# EEZ_DIB_MCU_r1B2.net
KiCad netlist of a schematic drawn in EAGLE
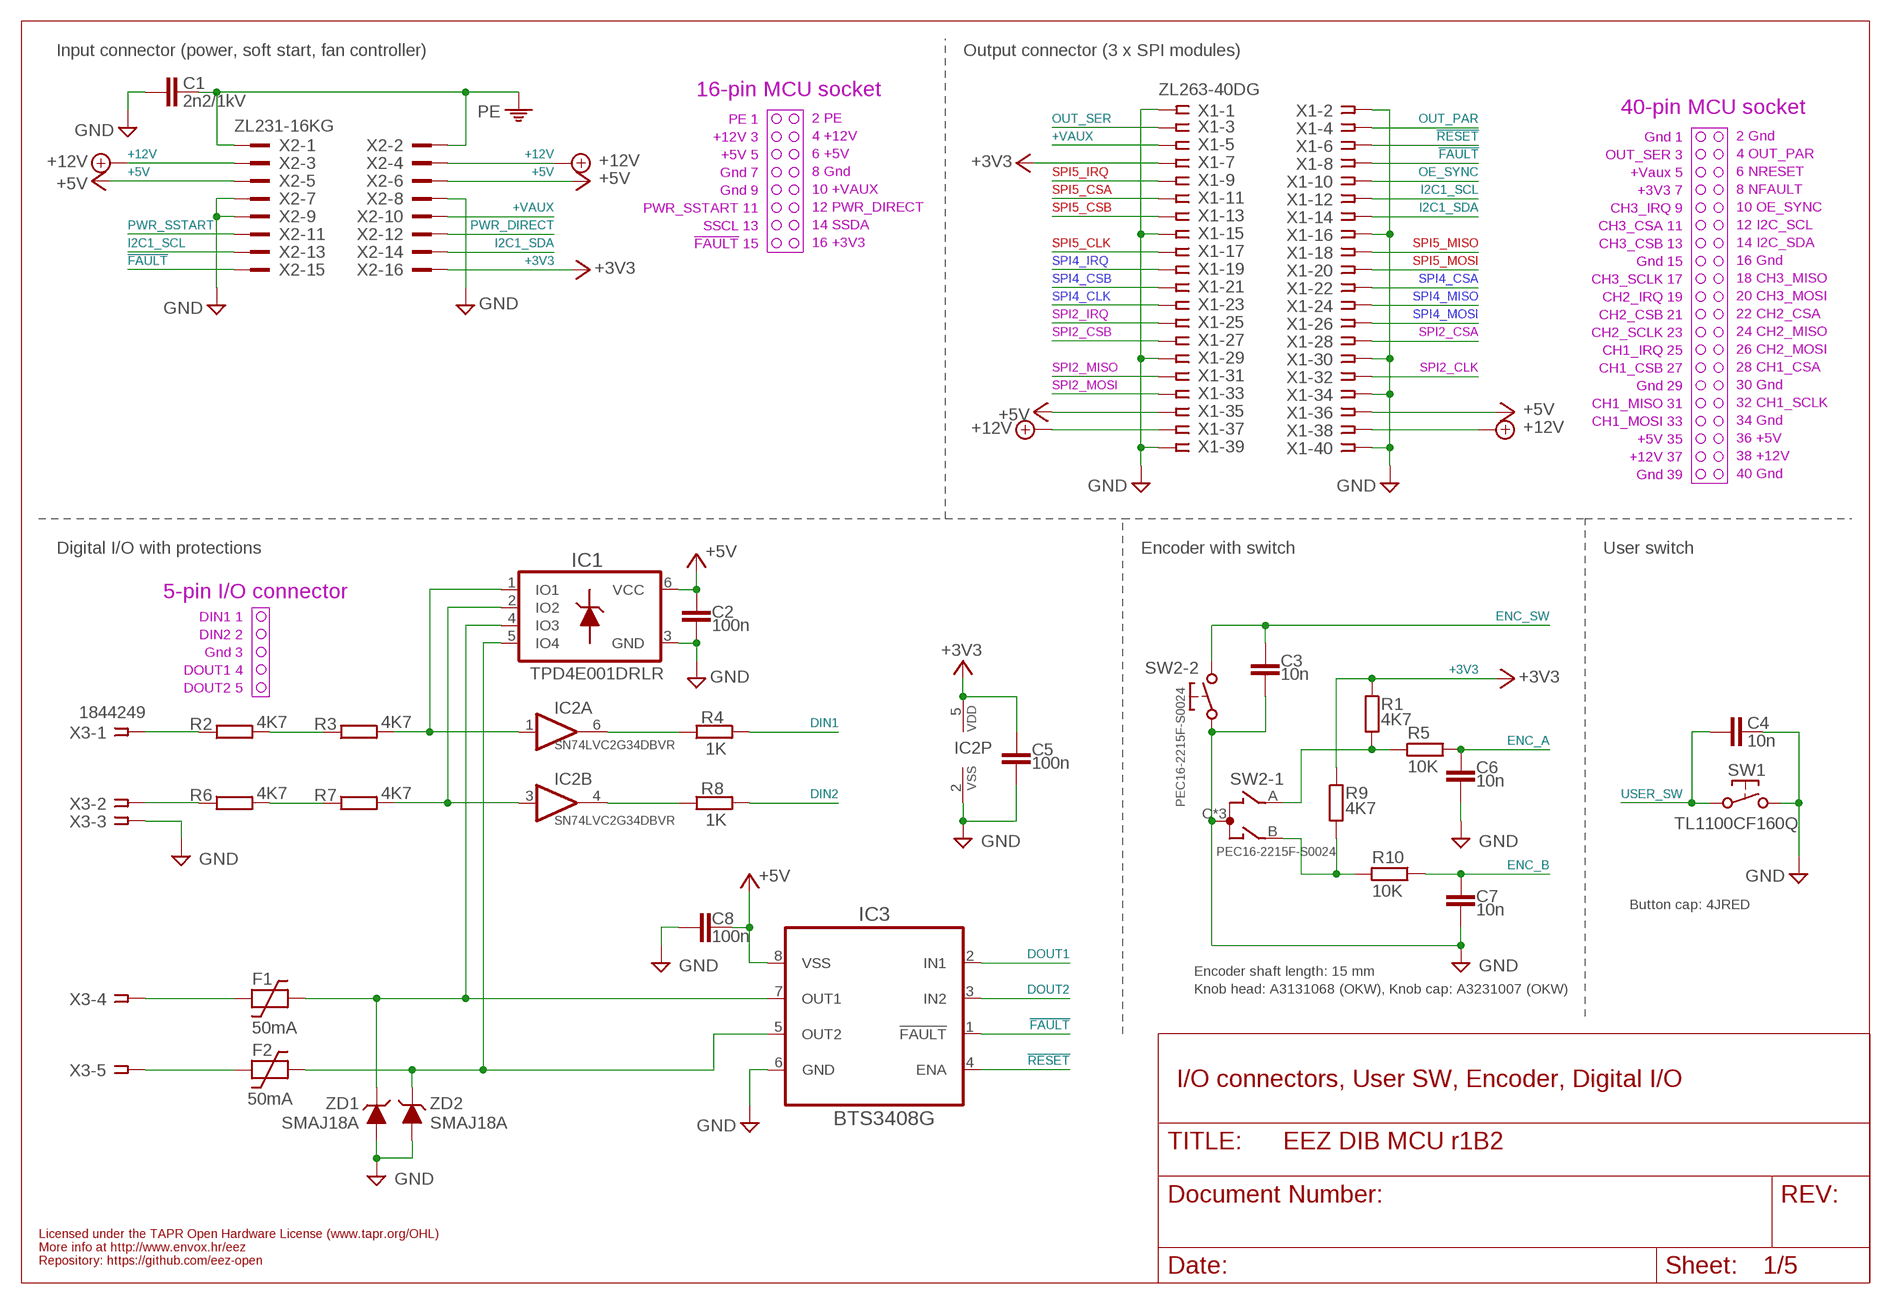
[diagram p0: schematic, sheet 1]
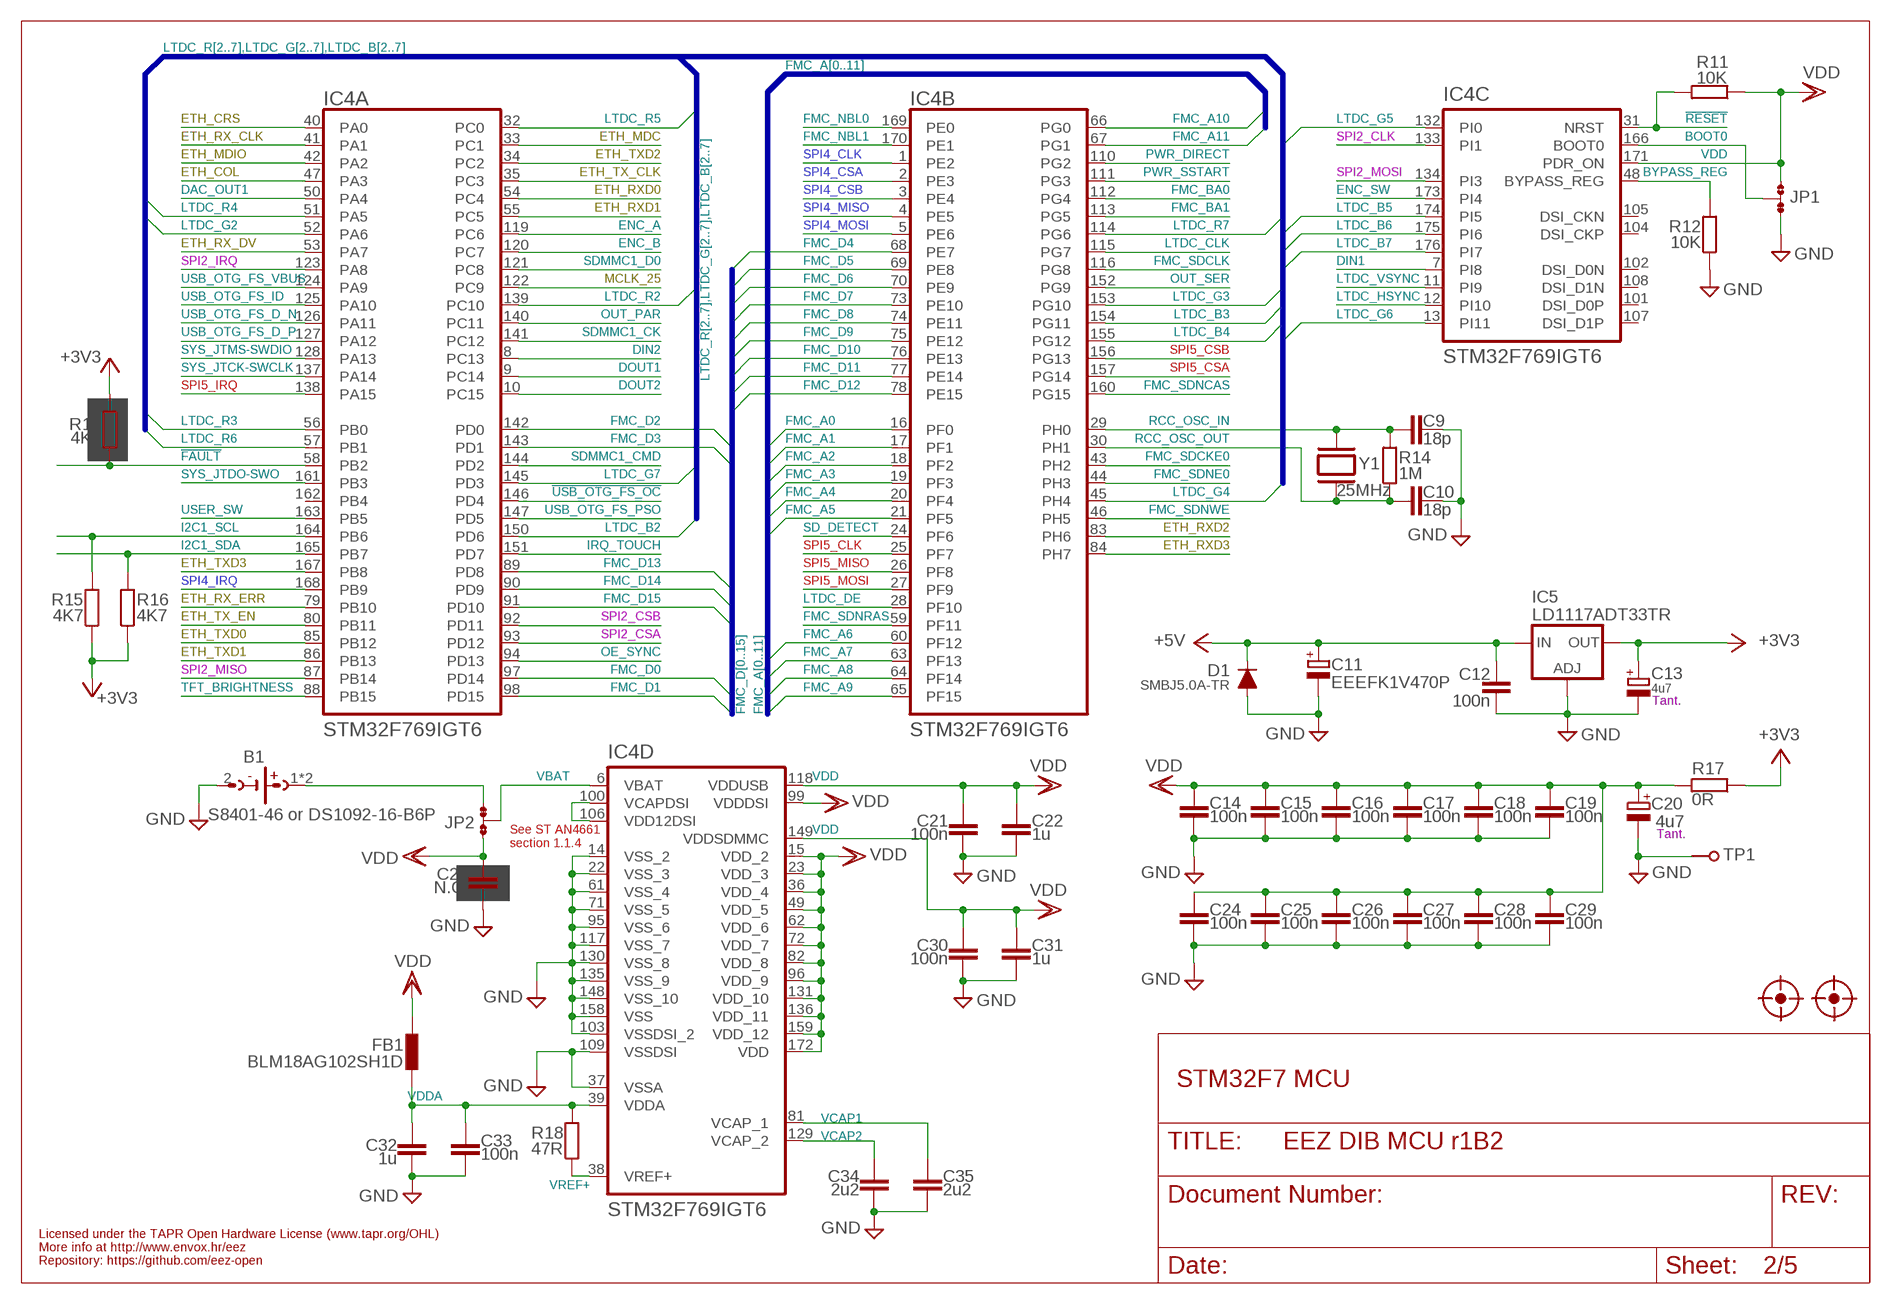
[diagram p1: schematic, sheet 2]
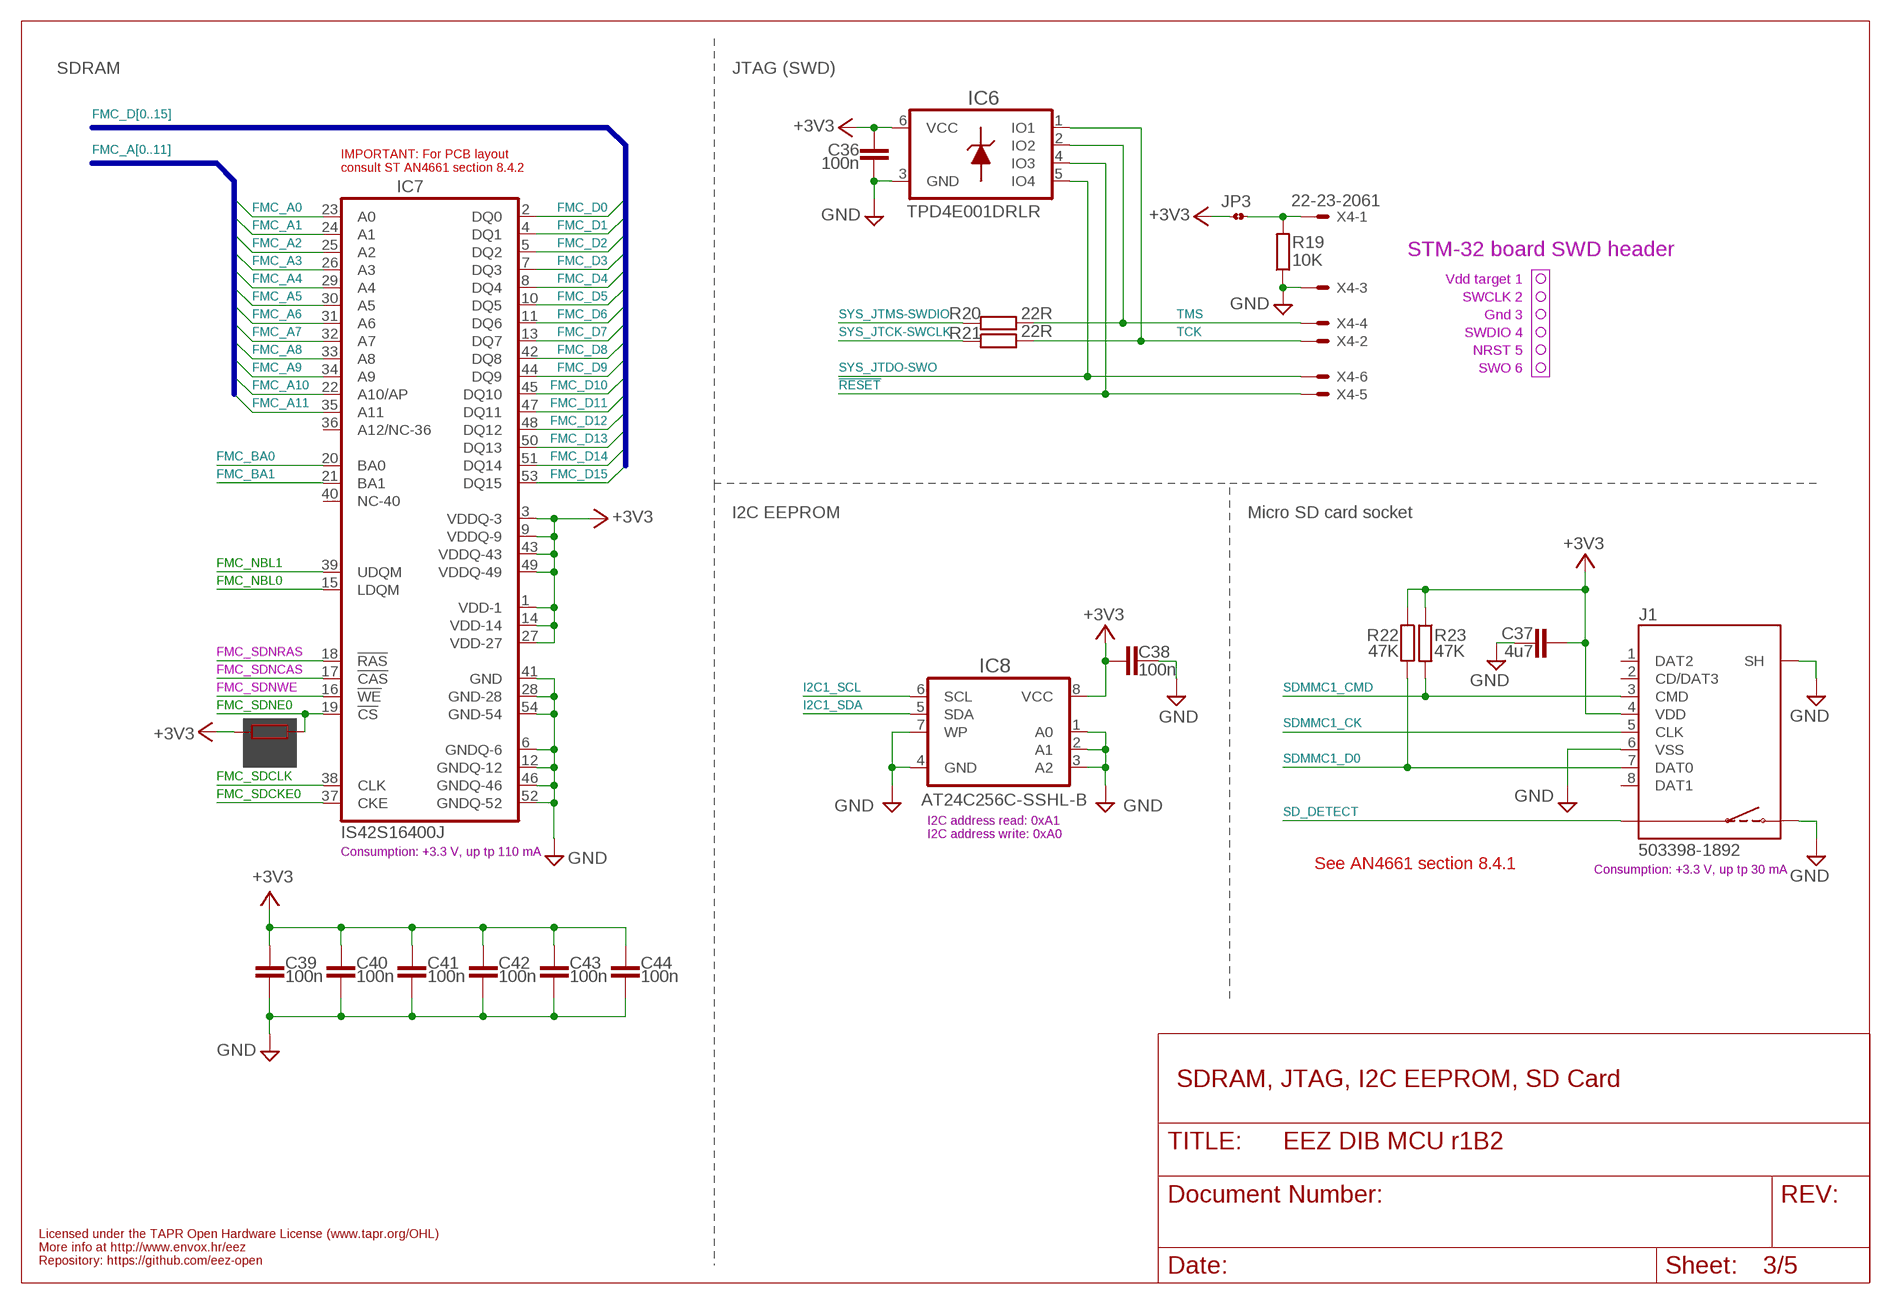
[diagram p2: schematic, sheet 3]
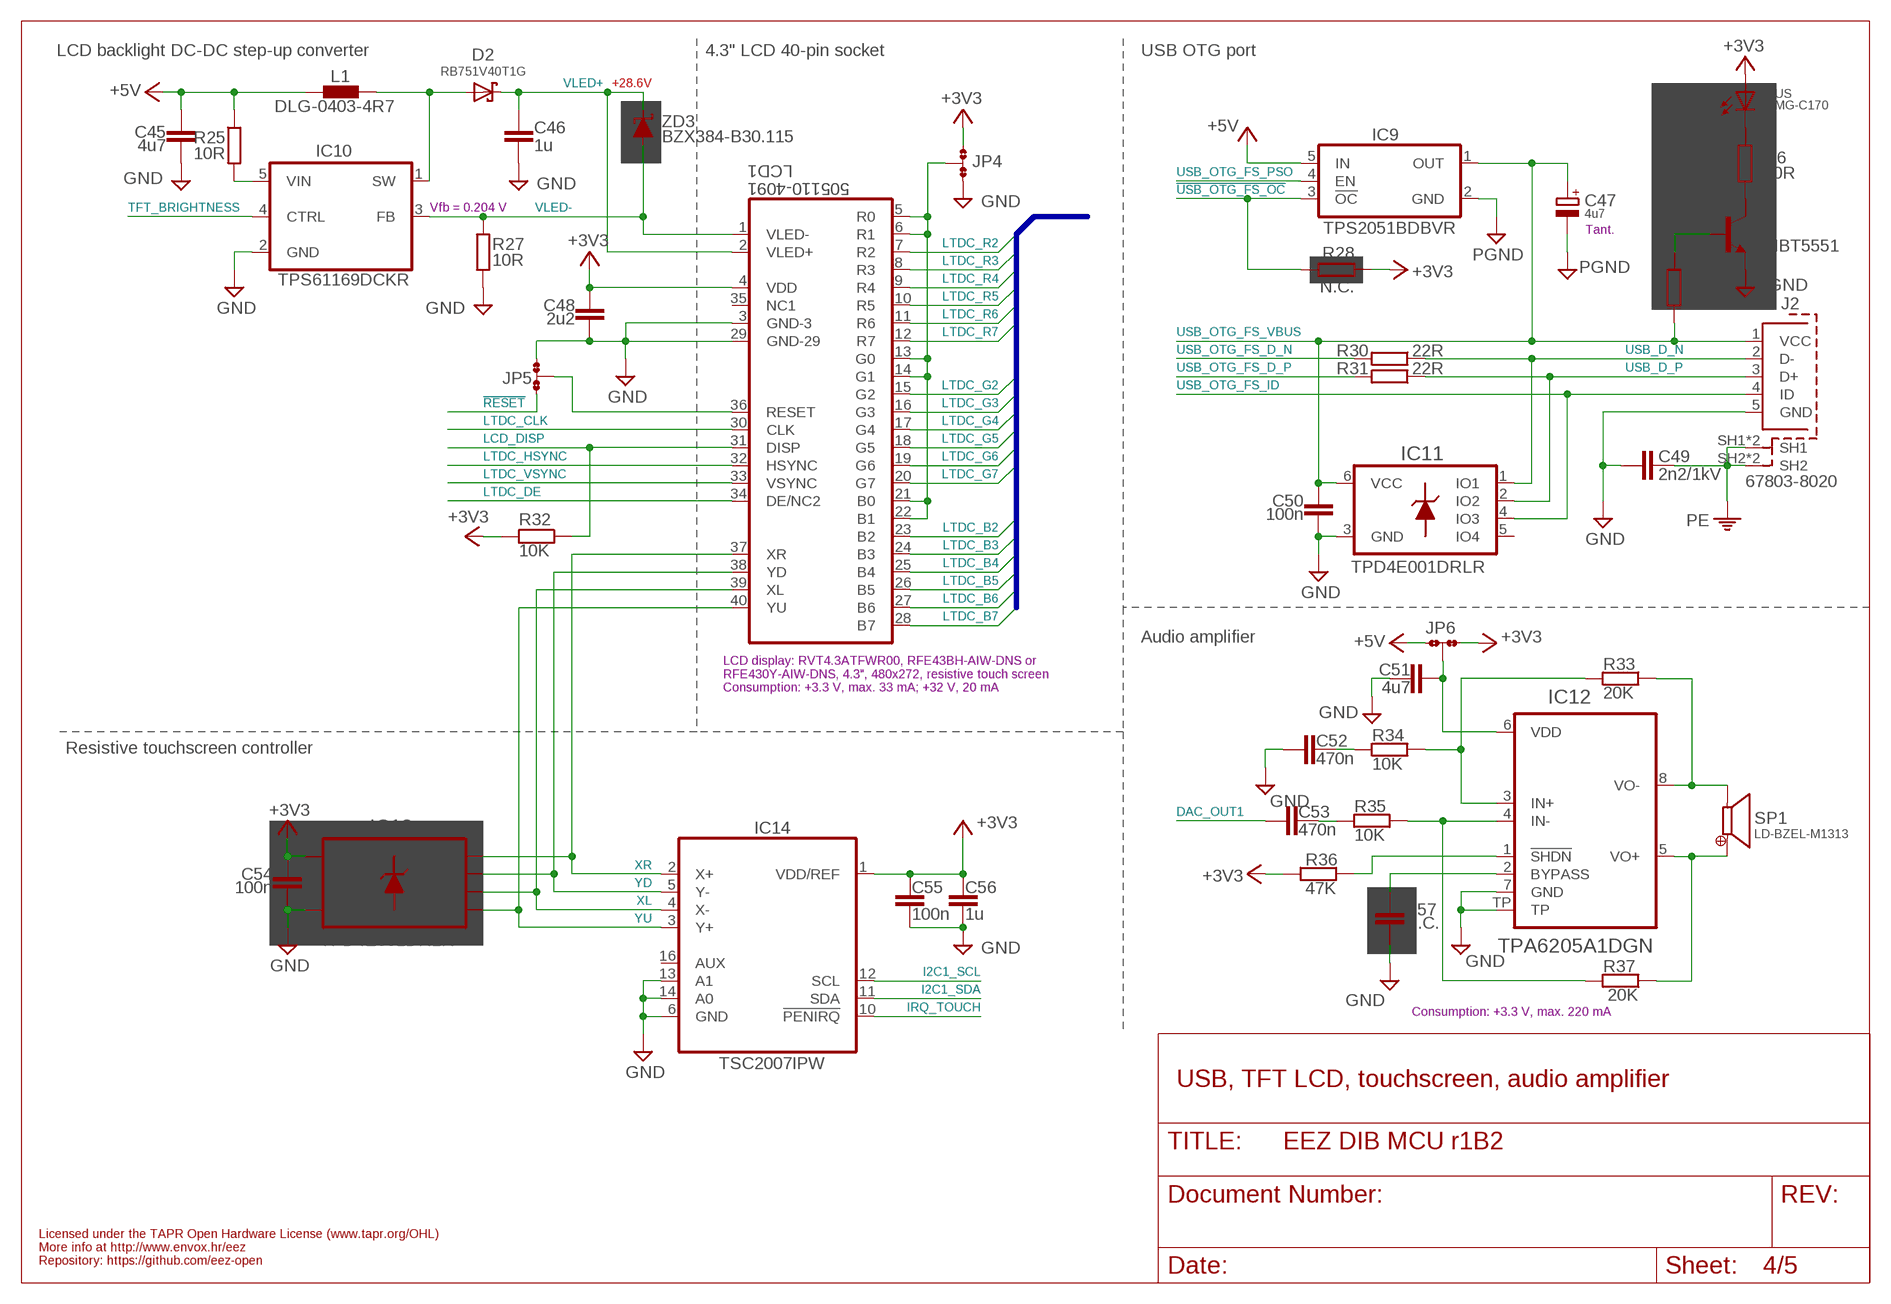
[diagram p3: schematic, sheet 4]
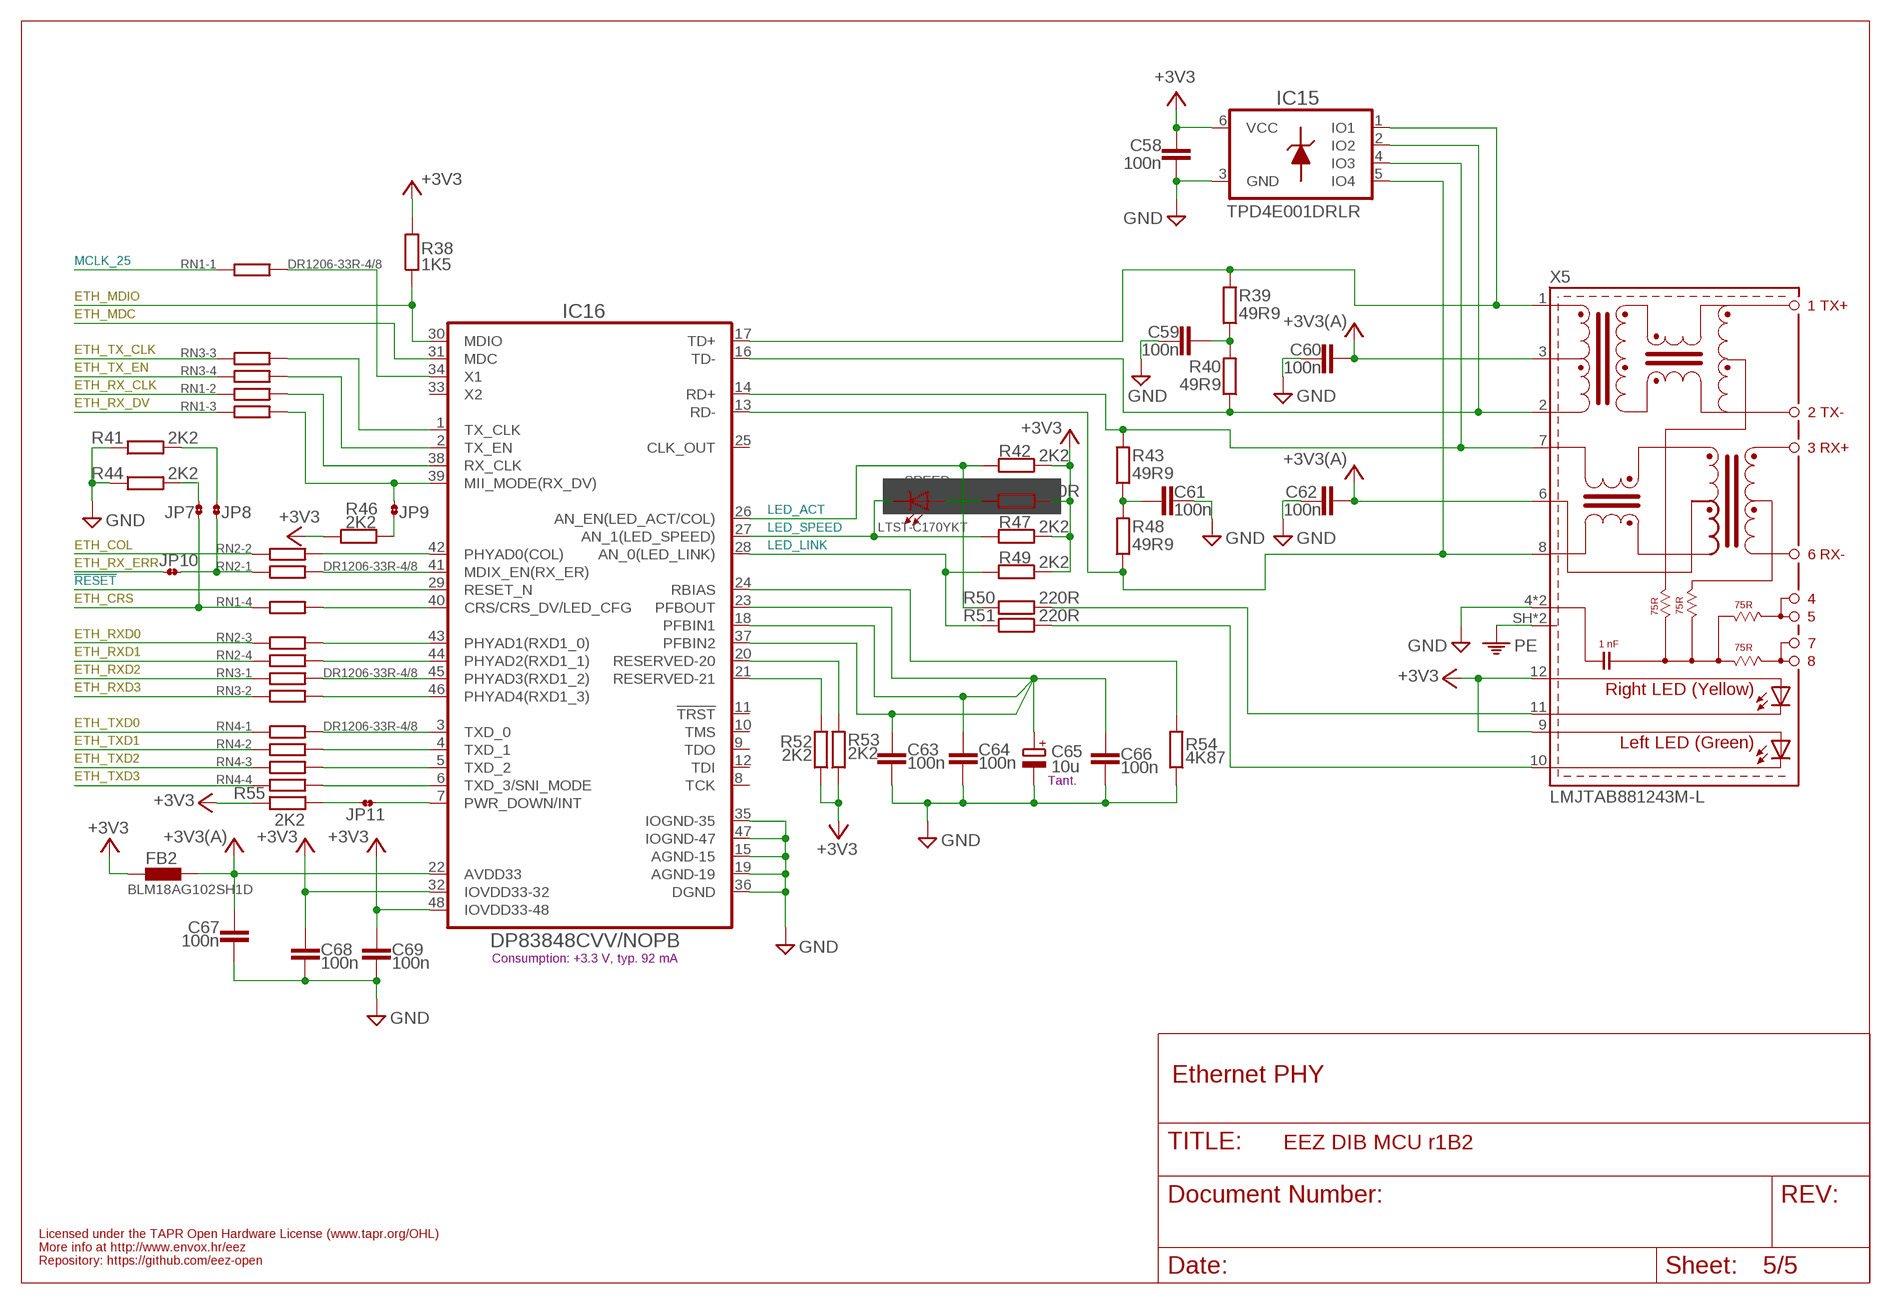
[diagram p4: schematic, sheet 5]

(export (version "E")
  (design (tool "Eeschema 10.0.6"))
  (components
    (comp (ref "C45")
      (value "4u7")
      (footprint "eagle-import:C1206")
      (libsource (lib "eagle-import") (part "C-EUC1206"))
    )
    (comp (ref "C46")
      (value "1u")
      (footprint "eagle-import:C0805")
      (libsource (lib "eagle-import") (part "C-EUC0805"))
    )
    (comp (ref "C47")
      (value "4u7")
      (footprint "eagle-import:EC1206")
      (libsource (lib "eagle-import") (part "ECAP1206"))
    )
    (comp (ref "C48")
      (value "2u2")
      (footprint "eagle-import:C0805")
      (libsource (lib "eagle-import") (part "C-EUC0805"))
    )
    (comp (ref "C49")
      (value "2n2/1kV")
      (footprint "eagle-import:C1210")
      (libsource (lib "eagle-import") (part "C-EUC1210"))
    )
    (comp (ref "C50")
      (value "100n")
      (footprint "eagle-import:C0603")
      (libsource (lib "eagle-import") (part "C-EUC0603"))
    )
    (comp (ref "C51")
      (value "4u7")
      (footprint "eagle-import:C1206")
      (libsource (lib "eagle-import") (part "C-EUC1206"))
    )
    (comp (ref "C52")
      (value "470n")
      (footprint "eagle-import:C0805")
      (libsource (lib "eagle-import") (part "C-EUC0805"))
    )
    (comp (ref "C53")
      (value "470n")
      (footprint "eagle-import:C0805")
      (libsource (lib "eagle-import") (part "C-EUC0805"))
    )
    (comp (ref "C54")
      (value "100n")
      (footprint "eagle-import:C0603")
      (libsource (lib "eagle-import") (part "C-EUC0603"))
    )
    (comp (ref "C55")
      (value "100n")
      (footprint "eagle-import:C0603")
      (libsource (lib "eagle-import") (part "C-EUC0603"))
    )
    (comp (ref "C56")
      (value "1u")
      (footprint "eagle-import:C0805")
      (libsource (lib "eagle-import") (part "C-EUC0805"))
    )
    (comp (ref "C57")
      (value "N.C.")
      (footprint "eagle-import:C0805")
      (libsource (lib "eagle-import") (part "C-EUC0805"))
    )
    (comp (ref "D2")
      (value "RB751V40T1G")
      (footprint "eagle-import:SOD323-R")
      (libsource (lib "eagle-import") (part "SCHOTTKYSOD-323R"))
    )
    (comp (ref "IC9")
      (value "TPS2051BDBVR")
      (footprint "eagle-import:DBV5")
      (libsource (lib "eagle-import") (part "TPS2051B"))
    )
    (comp (ref "IC10")
      (value "TPS61169DCKR")
      (footprint "eagle-import:DCK5")
      (fields (field (name "MANUFACTURER") "Texas Instruments"))
      (libsource (lib "eagle-import") (part "TPS61169DCKR"))
    )
    (comp (ref "IC11")
      (value "TPD4E001DRLR")
      (footprint "eagle-import:DRL6")
      (libsource (lib "eagle-import") (part "TPD4E001-DRL"))
    )
    (comp (ref "IC12")
      (value "TPA6205A1DGN")
      (footprint "eagle-import:SOP65P490X110-9N")
      (libsource (lib "eagle-import") (part "TPA6205"))
    )
    (comp (ref "IC13")
      (value "TPD4E001DRLR")
      (footprint "eagle-import:DRL6")
      (libsource (lib "eagle-import") (part "TPD4E001-DRL"))
    )
    (comp (ref "IC14")
      (value "TSC2007IPW")
      (footprint "eagle-import:PW(R-PDSO-G16)")
      (libsource (lib "eagle-import") (part "TSC2007IPW"))
    )
    (comp (ref "J2")
      (value "67803-8020")
      (footprint "eagle-import:678038020")
      (libsource (lib "eagle-import") (part "678038020"))
    )
    (comp (ref "JP4")
      (value "JP3-CUT")
      (footprint "eagle-import:JP3-CUT")
      (libsource (lib "eagle-import") (part "JP3-CUT"))
    )
    (comp (ref "JP5")
      (value "JP3-CUT")
      (footprint "eagle-import:JP3-CUT")
      (libsource (lib "eagle-import") (part "JP3-CUT"))
    )
    (comp (ref "JP6")
      (value "JP3-CUT")
      (footprint "eagle-import:JP3-CUT")
      (libsource (lib "eagle-import") (part "JP3-CUT"))
    )
    (comp (ref "L1")
      (value "DLG-0403-4R7")
      (footprint "eagle-import:DE0403")
      (libsource (lib "eagle-import") (part "DE0403"))
    )
    (comp (ref "LCD1")
      (value "505110-4091")
      (footprint "eagle-import:FPC_40")
      (libsource (lib "eagle-import") (part "RFE430Y-AIW-DNS"))
    )
    (comp (ref "Q1")
      (value "MMBT5551")
      (footprint "eagle-import:SOT23-BEC")
      (libsource (lib "eagle-import") (part "-NPN-SOT23-BECMMBT5551LT1"))
    )
    (comp (ref "R25")
      (value "10R")
      (footprint "eagle-import:R0805")
      (libsource (lib "eagle-import") (part "R-EU_R0805"))
    )
    (comp (ref "R26")
      (value "330R")
      (footprint "eagle-import:R0805")
      (libsource (lib "eagle-import") (part "R-EU_R0805"))
    )
    (comp (ref "R27")
      (value "10R")
      (footprint "eagle-import:R0805")
      (libsource (lib "eagle-import") (part "R-EU_R0805"))
    )
    (comp (ref "R28")
      (value "N.C.")
      (footprint "eagle-import:R0805")
      (libsource (lib "eagle-import") (part "R-EU_R0805"))
    )
    (comp (ref "R29")
      (value "47K")
      (footprint "eagle-import:R0805")
      (libsource (lib "eagle-import") (part "R-EU_R0805"))
    )
    (comp (ref "R30")
      (value "22R")
      (footprint "eagle-import:R0805")
      (libsource (lib "eagle-import") (part "R-EU_R0805"))
    )
    (comp (ref "R31")
      (value "22R")
      (footprint "eagle-import:R0805")
      (libsource (lib "eagle-import") (part "R-EU_R0805"))
    )
    (comp (ref "R32")
      (value "10K")
      (footprint "eagle-import:R0805")
      (libsource (lib "eagle-import") (part "R-EU_R0805"))
    )
    (comp (ref "R33")
      (value "20K")
      (footprint "eagle-import:R0805")
      (libsource (lib "eagle-import") (part "R-EU_R0805"))
    )
    (comp (ref "R34")
      (value "10K")
      (footprint "eagle-import:R0805")
      (libsource (lib "eagle-import") (part "R-EU_R0805"))
    )
    (comp (ref "R35")
      (value "10K")
      (footprint "eagle-import:R0805")
      (libsource (lib "eagle-import") (part "R-EU_R0805"))
    )
    (comp (ref "R36")
      (value "47K")
      (footprint "eagle-import:R0805")
      (libsource (lib "eagle-import") (part "R-EU_R0805"))
    )
    (comp (ref "R37")
      (value "20K")
      (footprint "eagle-import:R0805")
      (libsource (lib "eagle-import") (part "R-EU_R0805"))
    )
    (comp (ref "SP1")
      (value "LD-BZEL-M1313")
      (footprint "eagle-import:LD-BZEL-M1313")
      (libsource (lib "eagle-import") (part "LD-BZEL-M1313"))
    )
    (comp (ref "VBUS")
      (value "HSMG-C170")
      (footprint "eagle-import:LED_0805")
      (libsource (lib "eagle-import") (part "LED0805"))
    )
    (comp (ref "ZD3")
      (value "BZX384-B30.115")
      (footprint "eagle-import:SOD323-W")
      (libsource (lib "eagle-import") (part "ZENER-DIODESOD323"))
    )
    (comp (ref "B1")
      (value "S8401-46 or DS1092-16-B6P")
      (footprint "eagle-import:S8401-46")
      (libsource (lib "eagle-import") (part "CELL_BATTERYVERT"))
    )
    (comp (ref "C9")
      (value "18p")
      (footprint "eagle-import:C0603")
      (libsource (lib "eagle-import") (part "C-EUC0603"))
    )
    (comp (ref "C10")
      (value "18p")
      (footprint "eagle-import:C0603")
      (libsource (lib "eagle-import") (part "C-EUC0603"))
    )
    (comp (ref "C11")
      (value "EEEFK1V470P")
      (footprint "eagle-import:CAPAE660X610N")
      (libsource (lib "eagle-import") (part "ECAPPANASONIC_H"))
    )
    (comp (ref "C12")
      (value "100n")
      (footprint "eagle-import:C0603")
      (libsource (lib "eagle-import") (part "C-EUC0603"))
    )
    (comp (ref "C13")
      (value "4u7")
      (footprint "eagle-import:EC1206")
      (libsource (lib "eagle-import") (part "ECAP1206"))
    )
    (comp (ref "C14")
      (value "100n")
      (footprint "eagle-import:C0603")
      (libsource (lib "eagle-import") (part "C-EUC0603"))
    )
    (comp (ref "C15")
      (value "100n")
      (footprint "eagle-import:C0603")
      (libsource (lib "eagle-import") (part "C-EUC0603"))
    )
    (comp (ref "C16")
      (value "100n")
      (footprint "eagle-import:C0603")
      (libsource (lib "eagle-import") (part "C-EUC0603"))
    )
    (comp (ref "C17")
      (value "100n")
      (footprint "eagle-import:C0603")
      (libsource (lib "eagle-import") (part "C-EUC0603"))
    )
    (comp (ref "C18")
      (value "100n")
      (footprint "eagle-import:C0603")
      (libsource (lib "eagle-import") (part "C-EUC0603"))
    )
    (comp (ref "C19")
      (value "100n")
      (footprint "eagle-import:C0603")
      (libsource (lib "eagle-import") (part "C-EUC0603"))
    )
    (comp (ref "C20")
      (value "4u7")
      (footprint "eagle-import:EC1206")
      (libsource (lib "eagle-import") (part "ECAP1206"))
    )
    (comp (ref "C21")
      (value "100n")
      (footprint "eagle-import:C0603")
      (libsource (lib "eagle-import") (part "C-EUC0603"))
    )
    (comp (ref "C22")
      (value "1u")
      (footprint "eagle-import:C0805")
      (libsource (lib "eagle-import") (part "C-EUC0805"))
    )
    (comp (ref "C23")
      (value "N.C.")
      (footprint "eagle-import:C0603")
      (libsource (lib "eagle-import") (part "C-EUC0603"))
    )
    (comp (ref "C24")
      (value "100n")
      (footprint "eagle-import:C0603")
      (libsource (lib "eagle-import") (part "C-EUC0603"))
    )
    (comp (ref "C25")
      (value "100n")
      (footprint "eagle-import:C0603")
      (libsource (lib "eagle-import") (part "C-EUC0603"))
    )
    (comp (ref "C26")
      (value "100n")
      (footprint "eagle-import:C0603")
      (libsource (lib "eagle-import") (part "C-EUC0603"))
    )
    (comp (ref "C27")
      (value "100n")
      (footprint "eagle-import:C0603")
      (libsource (lib "eagle-import") (part "C-EUC0603"))
    )
    (comp (ref "C28")
      (value "100n")
      (footprint "eagle-import:C0603")
      (libsource (lib "eagle-import") (part "C-EUC0603"))
    )
    (comp (ref "C29")
      (value "100n")
      (footprint "eagle-import:C0603")
      (libsource (lib "eagle-import") (part "C-EUC0603"))
    )
    (comp (ref "C30")
      (value "100n")
      (footprint "eagle-import:C0603")
      (libsource (lib "eagle-import") (part "C-EUC0603"))
    )
    (comp (ref "C31")
      (value "1u")
      (footprint "eagle-import:C0805")
      (libsource (lib "eagle-import") (part "C-EUC0805"))
    )
    (comp (ref "C32")
      (value "1u")
      (footprint "eagle-import:C0805")
      (libsource (lib "eagle-import") (part "C-EUC0805"))
    )
    (comp (ref "C33")
      (value "100n")
      (footprint "eagle-import:C0603")
      (libsource (lib "eagle-import") (part "C-EUC0603"))
    )
    (comp (ref "C34")
      (value "2u2")
      (footprint "eagle-import:C0805")
      (libsource (lib "eagle-import") (part "C-EUC0805"))
    )
    (comp (ref "C35")
      (value "2u2")
      (footprint "eagle-import:C0805")
      (libsource (lib "eagle-import") (part "C-EUC0805"))
    )
    (comp (ref "D1")
      (value "SMBJ5.0A-TR")
      (footprint "eagle-import:DO214AA")
      (libsource (lib "eagle-import") (part "DIODEDO214AA"))
    )
    (comp (ref "FB1")
      (value "BLM18AG102SH1D")
      (footprint "eagle-import:BEAD0603")
      (libsource (lib "eagle-import") (part "FERRITE_BEAD0603"))
    )
    (comp (ref "FM1")
      (value "FIDUCIAL")
      (footprint "eagle-import:FIDUCIAL")
      (libsource (lib "eagle-import") (part "FIDUCIAL"))
    )
    (comp (ref "FM2")
      (value "FIDUCIAL")
      (footprint "eagle-import:FIDUCIAL")
      (libsource (lib "eagle-import") (part "FIDUCIAL"))
    )
    (comp (ref "IC4")
      (value "STM32F769IGT6")
      (footprint "eagle-import:LQFP-176_24X24MM")
      (fields
        (field (name "MANUFACTURER_PART_NUMBER") "stm32f769ixt")
        (field (name "COPYRIGHT") "Copyright C 2016 Accelerated Designs. All rights reserved")
      )
      (libsource (lib "eagle-import") (part "STM32F769IXT"))
    )
    (comp (ref "IC5")
      (value "LD1117ADT33TR")
      (footprint "eagle-import:DPACK")
      (libsource (lib "eagle-import") (part "LD117A?DT33TR"))
    )
    (comp (ref "JP1")
      (value "JP3-CUT")
      (footprint "eagle-import:JP3-CUT")
      (libsource (lib "eagle-import") (part "JP3-CUT"))
    )
    (comp (ref "JP2")
      (value "JP3-CUT")
      (footprint "eagle-import:JP3-CUT")
      (libsource (lib "eagle-import") (part "JP3-CUT"))
    )
    (comp (ref "R11")
      (value "10K")
      (footprint "eagle-import:R0805")
      (libsource (lib "eagle-import") (part "R-EU_R0805"))
    )
    (comp (ref "R12")
      (value "10K")
      (footprint "eagle-import:R0805")
      (libsource (lib "eagle-import") (part "R-EU_R0805"))
    )
    (comp (ref "R13")
      (value "4K7")
      (footprint "eagle-import:R0805")
      (libsource (lib "eagle-import") (part "R-EU_R0805"))
    )
    (comp (ref "R14")
      (value "1M")
      (footprint "eagle-import:R0805")
      (libsource (lib "eagle-import") (part "R-EU_R0805"))
    )
    (comp (ref "R15")
      (value "4K7")
      (footprint "eagle-import:R0805")
      (libsource (lib "eagle-import") (part "R-EU_R0805"))
    )
    (comp (ref "R16")
      (value "4K7")
      (footprint "eagle-import:R0805")
      (libsource (lib "eagle-import") (part "R-EU_R0805"))
    )
    (comp (ref "R17")
      (value "0R")
      (footprint "eagle-import:R0805")
      (libsource (lib "eagle-import") (part "R-EU_R0805"))
    )
    (comp (ref "R18")
      (value "47R")
      (footprint "eagle-import:R0805")
      (libsource (lib "eagle-import") (part "R-EU_R0805"))
    )
    (comp (ref "TP1")
      (value "PCB_TEST_TABSHIELD")
      (footprint "eagle-import:PCB_SHIELD_TAB")
      (libsource (lib "eagle-import") (part "PCB_TEST_TABSHIELD"))
    )
    (comp (ref "Y1")
      (value "25MHz")
      (footprint "eagle-import:HC-49_4H")
      (libsource (lib "eagle-import") (part "XTALSMD"))
    )
    (comp (ref "C36")
      (value "100n")
      (footprint "eagle-import:C0603")
      (libsource (lib "eagle-import") (part "C-EUC0603"))
    )
    (comp (ref "C37")
      (value "4u7")
      (footprint "eagle-import:C1206")
      (libsource (lib "eagle-import") (part "C-EUC1206"))
    )
    (comp (ref "C38")
      (value "100n")
      (footprint "eagle-import:C0603")
      (libsource (lib "eagle-import") (part "C-EUC0603"))
    )
    (comp (ref "C39")
      (value "100n")
      (footprint "eagle-import:C0603")
      (libsource (lib "eagle-import") (part "C-EUC0603"))
    )
    (comp (ref "C40")
      (value "100n")
      (footprint "eagle-import:C0603")
      (libsource (lib "eagle-import") (part "C-EUC0603"))
    )
    (comp (ref "C41")
      (value "100n")
      (footprint "eagle-import:C0603")
      (libsource (lib "eagle-import") (part "C-EUC0603"))
    )
    (comp (ref "C42")
      (value "100n")
      (footprint "eagle-import:C0603")
      (libsource (lib "eagle-import") (part "C-EUC0603"))
    )
    (comp (ref "C43")
      (value "100n")
      (footprint "eagle-import:C0603")
      (libsource (lib "eagle-import") (part "C-EUC0603"))
    )
    (comp (ref "C44")
      (value "100n")
      (footprint "eagle-import:C0603")
      (libsource (lib "eagle-import") (part "C-EUC0603"))
    )
    (comp (ref "IC6")
      (value "TPD4E001DRLR")
      (footprint "eagle-import:DRL6")
      (libsource (lib "eagle-import") (part "TPD4E001-DRL"))
    )
    (comp (ref "IC7")
      (value "IS42S16400J")
      (footprint "eagle-import:TSOPII-54")
      (libsource (lib "eagle-import") (part "IS42S16400"))
    )
    (comp (ref "IC8")
      (value "AT24C256C-SSHL-B")
      (footprint "eagle-import:SOIC127P600X173-8N")
      (libsource (lib "eagle-import") (part "AT24CXXSOIC8"))
    )
    (comp (ref "J1")
      (value "503398-1892")
      (footprint "eagle-import:5033981892")
      (libsource (lib "eagle-import") (part "5033981892"))
    )
    (comp (ref "JP3")
      (value "JP2-CUT")
      (footprint "eagle-import:JP2-CUT")
      (libsource (lib "eagle-import") (part "JP2-CUT"))
    )
    (comp (ref "R19")
      (value "10K")
      (footprint "eagle-import:R0805")
      (libsource (lib "eagle-import") (part "R-EU_R0805"))
    )
    (comp (ref "R20")
      (value "22R")
      (footprint "eagle-import:R0805")
      (libsource (lib "eagle-import") (part "R-EU_R0805"))
    )
    (comp (ref "R21")
      (value "22R")
      (footprint "eagle-import:R0805")
      (libsource (lib "eagle-import") (part "R-EU_R0805"))
    )
    (comp (ref "R22")
      (value "47K")
      (footprint "eagle-import:R0805")
      (libsource (lib "eagle-import") (part "R-EU_R0805"))
    )
    (comp (ref "R23")
      (value "47K")
      (footprint "eagle-import:R0805")
      (libsource (lib "eagle-import") (part "R-EU_R0805"))
    )
    (comp (ref "R24")
      (value "N.C.")
      (footprint "eagle-import:R0805")
      (libsource (lib "eagle-import") (part "R-EU_R0805"))
    )
    (comp (ref "X4")
      (value "22-23-2061")
      (footprint "eagle-import:22-23-2061")
      (fields (field (name "MF") "MOLEX"))
      (libsource (lib "eagle-import") (part "22-23-2061"))
    )
    (comp (ref "C58")
      (value "100n")
      (footprint "eagle-import:C0603")
      (libsource (lib "eagle-import") (part "C-EUC0603"))
    )
    (comp (ref "C59")
      (value "100n")
      (footprint "eagle-import:C0603")
      (libsource (lib "eagle-import") (part "C-EUC0603"))
    )
    (comp (ref "C60")
      (value "100n")
      (footprint "eagle-import:C0603")
      (libsource (lib "eagle-import") (part "C-EUC0603"))
    )
    (comp (ref "C61")
      (value "100n")
      (footprint "eagle-import:C0603")
      (libsource (lib "eagle-import") (part "C-EUC0603"))
    )
    (comp (ref "C62")
      (value "100n")
      (footprint "eagle-import:C0603")
      (libsource (lib "eagle-import") (part "C-EUC0603"))
    )
    (comp (ref "C63")
      (value "100n")
      (footprint "eagle-import:C0603")
      (libsource (lib "eagle-import") (part "C-EUC0603"))
    )
    (comp (ref "C64")
      (value "100n")
      (footprint "eagle-import:C0603")
      (libsource (lib "eagle-import") (part "C-EUC0603"))
    )
    (comp (ref "C65")
      (value "10u")
      (footprint "eagle-import:EC1206")
      (libsource (lib "eagle-import") (part "ECAP1206"))
    )
    (comp (ref "C66")
      (value "100n")
      (footprint "eagle-import:C0603")
      (libsource (lib "eagle-import") (part "C-EUC0603"))
    )
    (comp (ref "C67")
      (value "100n")
      (footprint "eagle-import:C0603")
      (libsource (lib "eagle-import") (part "C-EUC0603"))
    )
    (comp (ref "C68")
      (value "100n")
      (footprint "eagle-import:C0603")
      (libsource (lib "eagle-import") (part "C-EUC0603"))
    )
    (comp (ref "C69")
      (value "100n")
      (footprint "eagle-import:C0603")
      (libsource (lib "eagle-import") (part "C-EUC0603"))
    )
    (comp (ref "FB2")
      (value "BLM18AG102SH1D")
      (footprint "eagle-import:BEAD0603")
      (libsource (lib "eagle-import") (part "FERRITE_BEAD0603"))
    )
    (comp (ref "IC15")
      (value "TPD4E001DRLR")
      (footprint "eagle-import:DRL6")
      (libsource (lib "eagle-import") (part "TPD4E001-DRL"))
    )
    (comp (ref "IC16")
      (value "DP83848CVV/NOPB")
      (footprint "eagle-import:PT48")
      (libsource (lib "eagle-import") (part "DP83848CVV/NOPB"))
    )
    (comp (ref "JP7")
      (value "JP2-CUT")
      (footprint "eagle-import:JP2-CUT")
      (libsource (lib "eagle-import") (part "JP2-CUT"))
    )
    (comp (ref "JP8")
      (value "JP2-CUT")
      (footprint "eagle-import:JP2-CUT")
      (libsource (lib "eagle-import") (part "JP2-CUT"))
    )
    (comp (ref "JP9")
      (value "JP2-CUT")
      (footprint "eagle-import:JP2-CUT")
      (libsource (lib "eagle-import") (part "JP2-CUT"))
    )
    (comp (ref "JP10")
      (value "JP2-NOCUT")
      (footprint "eagle-import:JP2-NOCUT")
      (libsource (lib "eagle-import") (part "JP2-NOCUT"))
    )
    (comp (ref "JP11")
      (value "JP2-NOCUT")
      (footprint "eagle-import:JP2-NOCUT")
      (libsource (lib "eagle-import") (part "JP2-NOCUT"))
    )
    (comp (ref "R38")
      (value "1K5")
      (footprint "eagle-import:R0805")
      (libsource (lib "eagle-import") (part "R-EU_R0805"))
    )
    (comp (ref "R39")
      (value "49R9")
      (footprint "eagle-import:R0805")
      (libsource (lib "eagle-import") (part "R-EU_R0805"))
    )
    (comp (ref "R40")
      (value "49R9")
      (footprint "eagle-import:R0805")
      (libsource (lib "eagle-import") (part "R-EU_R0805"))
    )
    (comp (ref "R41")
      (value "2K2")
      (footprint "eagle-import:R0805")
      (libsource (lib "eagle-import") (part "R-EU_R0805"))
    )
    (comp (ref "R42")
      (value "2K2")
      (footprint "eagle-import:R0805")
      (libsource (lib "eagle-import") (part "R-EU_R0805"))
    )
    (comp (ref "R43")
      (value "49R9")
      (footprint "eagle-import:R0805")
      (libsource (lib "eagle-import") (part "R-EU_R0805"))
    )
    (comp (ref "R44")
      (value "2K2")
      (footprint "eagle-import:R0805")
      (libsource (lib "eagle-import") (part "R-EU_R0805"))
    )
    (comp (ref "R45")
      (value "220R")
      (footprint "eagle-import:R0805")
      (libsource (lib "eagle-import") (part "R-EU_R0805"))
    )
    (comp (ref "R46")
      (value "2K2")
      (footprint "eagle-import:R0805")
      (libsource (lib "eagle-import") (part "R-EU_R0805"))
    )
    (comp (ref "R47")
      (value "2K2")
      (footprint "eagle-import:R0805")
      (libsource (lib "eagle-import") (part "R-EU_R0805"))
    )
    (comp (ref "R48")
      (value "49R9")
      (footprint "eagle-import:R0805")
      (libsource (lib "eagle-import") (part "R-EU_R0805"))
    )
    (comp (ref "R49")
      (value "2K2")
      (footprint "eagle-import:R0805")
      (libsource (lib "eagle-import") (part "R-EU_R0805"))
    )
    (comp (ref "R50")
      (value "220R")
      (footprint "eagle-import:R0805")
      (libsource (lib "eagle-import") (part "R-EU_R0805"))
    )
    (comp (ref "R51")
      (value "220R")
      (footprint "eagle-import:R0805")
      (libsource (lib "eagle-import") (part "R-EU_R0805"))
    )
    (comp (ref "R52")
      (value "2K2")
      (footprint "eagle-import:R0805")
      (libsource (lib "eagle-import") (part "R-EU_R0805"))
    )
    (comp (ref "R53")
      (value "2K2")
      (footprint "eagle-import:R0805")
      (libsource (lib "eagle-import") (part "R-EU_R0805"))
    )
    (comp (ref "R54")
      (value "4K87")
      (footprint "eagle-import:R0805")
      (libsource (lib "eagle-import") (part "R-EU_R0805"))
    )
    (comp (ref "R55")
      (value "2K2")
      (footprint "eagle-import:R0805")
      (libsource (lib "eagle-import") (part "R-EU_R0805"))
    )
    (comp (ref "RN1")
      (value "DR1206-33R-4/8")
      (footprint "eagle-import:CAY16")
      (libsource (lib "eagle-import") (part "R_ARRAY4"))
    )
    (comp (ref "RN2")
      (value "DR1206-33R-4/8")
      (footprint "eagle-import:CAY16")
      (libsource (lib "eagle-import") (part "R_ARRAY4"))
    )
    (comp (ref "RN3")
      (value "DR1206-33R-4/8")
      (footprint "eagle-import:CAY16")
      (libsource (lib "eagle-import") (part "R_ARRAY4"))
    )
    (comp (ref "RN4")
      (value "DR1206-33R-4/8")
      (footprint "eagle-import:CAY16")
      (libsource (lib "eagle-import") (part "R_ARRAY4"))
    )
    (comp (ref "SPEED")
      (value "LTST-C170YKT")
      (footprint "eagle-import:LED_0805")
      (libsource (lib "eagle-import") (part "LED0805"))
    )
    (comp (ref "X5")
      (value "LMJTAB881243M-L")
      (footprint "eagle-import:RJ45-TRAFO-LED")
      (libsource (lib "eagle-import") (part "RJ45-TRAFO-LED"))
    )
    (comp (ref "C1")
      (value "2n2/1kV")
      (footprint "eagle-import:C1210")
      (libsource (lib "eagle-import") (part "C-EUC1210"))
    )
    (comp (ref "C2")
      (value "100n")
      (footprint "eagle-import:C0603")
      (libsource (lib "eagle-import") (part "C-EUC0603"))
    )
    (comp (ref "C3")
      (value "10n")
      (footprint "eagle-import:C0805")
      (libsource (lib "eagle-import") (part "C-EUC0805"))
    )
    (comp (ref "C4")
      (value "10n")
      (footprint "eagle-import:C0805")
      (libsource (lib "eagle-import") (part "C-EUC0805"))
    )
    (comp (ref "C5")
      (value "100n")
      (footprint "eagle-import:C0603")
      (libsource (lib "eagle-import") (part "C-EUC0603"))
    )
    (comp (ref "C6")
      (value "10n")
      (footprint "eagle-import:C0805")
      (libsource (lib "eagle-import") (part "C-EUC0805"))
    )
    (comp (ref "C7")
      (value "10n")
      (footprint "eagle-import:C0805")
      (libsource (lib "eagle-import") (part "C-EUC0805"))
    )
    (comp (ref "C8")
      (value "100n")
      (footprint "eagle-import:C0603")
      (libsource (lib "eagle-import") (part "C-EUC0603"))
    )
    (comp (ref "F1")
      (value "50mA")
      (footprint "eagle-import:F1210")
      (libsource (lib "eagle-import") (part "FUSE_RESETTABLE21210"))
    )
    (comp (ref "F2")
      (value "50mA")
      (footprint "eagle-import:F1210")
      (libsource (lib "eagle-import") (part "FUSE_RESETTABLE21210"))
    )
    (comp (ref "IC1")
      (value "TPD4E001DRLR")
      (footprint "eagle-import:DRL6")
      (libsource (lib "eagle-import") (part "TPD4E001-DRL"))
    )
    (comp (ref "IC2")
      (value "SN74LVC2G34DBVR")
      (footprint "eagle-import:DBV6")
      (libsource (lib "eagle-import") (part "SN74LVC2G34DBVR"))
    )
    (comp (ref "IC3")
      (value "BTS3408G")
      (footprint "eagle-import:SOIC127P600X173-8N")
      (libsource (lib "eagle-import") (part "BTS3408G"))
    )
    (comp (ref "R1")
      (value "4K7")
      (footprint "eagle-import:R0805")
      (libsource (lib "eagle-import") (part "R-EU_R0805"))
    )
    (comp (ref "R2")
      (value "4K7")
      (footprint "eagle-import:R0805")
      (libsource (lib "eagle-import") (part "R-EU_R0805"))
    )
    (comp (ref "R3")
      (value "4K7")
      (footprint "eagle-import:R0805")
      (libsource (lib "eagle-import") (part "R-EU_R0805"))
    )
    (comp (ref "R4")
      (value "1K")
      (footprint "eagle-import:R0805")
      (libsource (lib "eagle-import") (part "R-EU_R0805"))
    )
    (comp (ref "R5")
      (value "10K")
      (footprint "eagle-import:R0805")
      (libsource (lib "eagle-import") (part "R-EU_R0805"))
    )
    (comp (ref "R6")
      (value "4K7")
      (footprint "eagle-import:R0805")
      (libsource (lib "eagle-import") (part "R-EU_R0805"))
    )
    (comp (ref "R7")
      (value "4K7")
      (footprint "eagle-import:R0805")
      (libsource (lib "eagle-import") (part "R-EU_R0805"))
    )
    (comp (ref "R8")
      (value "1K")
      (footprint "eagle-import:R0805")
      (libsource (lib "eagle-import") (part "R-EU_R0805"))
    )
    (comp (ref "R9")
      (value "4K7")
      (footprint "eagle-import:R0805")
      (libsource (lib "eagle-import") (part "R-EU_R0805"))
    )
    (comp (ref "R10")
      (value "10K")
      (footprint "eagle-import:R0805")
      (libsource (lib "eagle-import") (part "R-EU_R0805"))
    )
    (comp (ref "SW1")
      (value "TL1100CF160Q")
      (footprint "eagle-import:TL1100C")
      (libsource (lib "eagle-import") (part "TL1100C"))
    )
    (comp (ref "SW2")
      (value "PEC16-2215F-S0024")
      (footprint "eagle-import:PEC16-2215F")
      (libsource (lib "eagle-import") (part "ENCODER_SW-PEC16"))
    )
    (comp (ref "X1")
      (value "ZL263-40DG")
      (footprint "eagle-import:ZL263-40DG")
      (libsource (lib "eagle-import") (part "ZL263-40DG"))
    )
    (comp (ref "X2")
      (value "ZL231-16KG")
      (footprint "eagle-import:ML16L")
      (libsource (lib "eagle-import") (part "IDC-16PIN-ANGLED"))
    )
    (comp (ref "X3")
      (value "1844249")
      (footprint "eagle-import:MC1,5_5-G-3,5")
      (libsource (lib "eagle-import") (part "MC1,5/5-G-3,5"))
    )
    (comp (ref "ZD1")
      (value "SMAJ18A")
      (footprint "eagle-import:DO214AC")
      (libsource (lib "eagle-import") (part "PSMAXX"))
    )
    (comp (ref "ZD2")
      (value "SMAJ18A")
      (footprint "eagle-import:DO214AC")
      (libsource (lib "eagle-import") (part "PSMAXX"))
    )
  )
  (nets
    (net (code "1") (name "+3V3") (class "Default")
      (node (ref "C13") (pin "+") (pinfunction "+_+") (pintype "passive"))
      (node (ref "C36") (pin "1") (pinfunction "1_1") (pintype "passive"))
      (node (ref "C37") (pin "1") (pinfunction "1_1") (pintype "passive"))
      (node (ref "C38") (pin "2") (pinfunction "2_2") (pintype "passive"))
      (node (ref "C39") (pin "1") (pinfunction "1_1") (pintype "passive"))
      (node (ref "C40") (pin "1") (pinfunction "1_1") (pintype "passive"))
      (node (ref "C41") (pin "1") (pinfunction "1_1") (pintype "passive"))
      (node (ref "C42") (pin "1") (pinfunction "1_1") (pintype "passive"))
      (node (ref "C43") (pin "1") (pinfunction "1_1") (pintype "passive"))
      (node (ref "C44") (pin "1") (pinfunction "1_1") (pintype "passive"))
      (node (ref "C48") (pin "1") (pinfunction "1_1") (pintype "passive"))
      (node (ref "C5") (pin "1") (pinfunction "1_1") (pintype "passive"))
      (node (ref "C54") (pin "2") (pinfunction "2_2") (pintype "passive"))
      (node (ref "C55") (pin "2") (pinfunction "2_2") (pintype "passive"))
      (node (ref "C56") (pin "2") (pinfunction "2_2") (pintype "passive"))
      (node (ref "C58") (pin "1") (pinfunction "1_1") (pintype "passive"))
      (node (ref "C68") (pin "1") (pinfunction "1_1") (pintype "passive"))
      (node (ref "C69") (pin "1") (pinfunction "1_1") (pintype "passive"))
      (node (ref "FB2") (pin "P$1") (pinfunction "1_P$1") (pintype "passive"))
      (node (ref "IC13") (pin "6") (pinfunction "VCC_6") (pintype "passive"))
      (node (ref "IC14") (pin "1") (pinfunction "VDD/REF_1") (pintype "passive"))
      (node (ref "IC15") (pin "6") (pinfunction "VCC_6") (pintype "passive"))
      (node (ref "IC16") (pin "32") (pinfunction "IOVDD33-32_32") (pintype "power_in"))
      (node (ref "IC16") (pin "48") (pinfunction "IOVDD33-48_48") (pintype "power_in"))
      (node (ref "IC2") (pin "5") (pinfunction "VDD_5") (pintype "power_in"))
      (node (ref "IC5") (pin "4") (pinfunction "OUT_4") (pintype "passive"))
      (node (ref "IC6") (pin "6") (pinfunction "VCC_6") (pintype "passive"))
      (node (ref "IC7") (pin "1") (pinfunction "VDD-1_1") (pintype "power_in"))
      (node (ref "IC7") (pin "14") (pinfunction "VDD-14_14") (pintype "power_in"))
      (node (ref "IC7") (pin "27") (pinfunction "VDD-27_27") (pintype "power_in"))
      (node (ref "IC7") (pin "3") (pinfunction "VDDQ-3_3") (pintype "power_in"))
      (node (ref "IC7") (pin "43") (pinfunction "VDDQ-43_43") (pintype "power_in"))
      (node (ref "IC7") (pin "49") (pinfunction "VDDQ-49_49") (pintype "power_in"))
      (node (ref "IC7") (pin "9") (pinfunction "VDDQ-9_9") (pintype "power_in"))
      (node (ref "IC8") (pin "8") (pinfunction "VCC_8") (pintype "power_in"))
      (node (ref "J1") (pin "4") (pinfunction "VDD_4") (pintype "power_in"))
      (node (ref "JP3") (pin "1") (pinfunction "1_1") (pintype "passive"))
      (node (ref "JP4") (pin "NO") (pinfunction "NO_NO") (pintype "passive"))
      (node (ref "JP6") (pin "NC") (pinfunction "NC_NC") (pintype "passive"))
      (node (ref "LCD1") (pin "4") (pinfunction "VDD_4") (pintype "power_in"))
      (node (ref "R1") (pin "1") (pinfunction "1_1") (pintype "passive"))
      (node (ref "R13") (pin "1") (pinfunction "1_1") (pintype "passive"))
      (node (ref "R15") (pin "1") (pinfunction "1_1") (pintype "passive"))
      (node (ref "R16") (pin "1") (pinfunction "1_1") (pintype "passive"))
      (node (ref "R17") (pin "1") (pinfunction "1_1") (pintype "passive"))
      (node (ref "R22") (pin "1") (pinfunction "1_1") (pintype "passive"))
      (node (ref "R23") (pin "1") (pinfunction "1_1") (pintype "passive"))
      (node (ref "R24") (pin "1") (pinfunction "1_1") (pintype "passive"))
      (node (ref "R28") (pin "2") (pinfunction "2_2") (pintype "passive"))
      (node (ref "R32") (pin "2") (pinfunction "2_2") (pintype "passive"))
      (node (ref "R36") (pin "2") (pinfunction "2_2") (pintype "passive"))
      (node (ref "R38") (pin "2") (pinfunction "2_2") (pintype "passive"))
      (node (ref "R42") (pin "1") (pinfunction "1_1") (pintype "passive"))
      (node (ref "R45") (pin "1") (pinfunction "1_1") (pintype "passive"))
      (node (ref "R46") (pin "1") (pinfunction "1_1") (pintype "passive"))
      (node (ref "R47") (pin "1") (pinfunction "1_1") (pintype "passive"))
      (node (ref "R49") (pin "1") (pinfunction "1_1") (pintype "passive"))
      (node (ref "R52") (pin "1") (pinfunction "1_1") (pintype "passive"))
      (node (ref "R53") (pin "1") (pinfunction "1_1") (pintype "passive"))
      (node (ref "R55") (pin "1") (pinfunction "1_1") (pintype "passive"))
      (node (ref "R9") (pin "1") (pinfunction "1_1") (pintype "passive"))
      (node (ref "VBUS") (pin "A") (pinfunction "A_A") (pintype "passive"))
      (node (ref "X1") (pin "7") (pinfunction "1_7") (pintype "passive"))
      (node (ref "X2") (pin "16") (pinfunction "1_16") (pintype "passive"))
      (node (ref "X5") (pin "12") (pinfunction "YELLOW_A_12") (pintype "passive"))
      (node (ref "X5") (pin "9") (pinfunction "GREEN-A_9") (pintype "passive"))
    )
    (net (code "2") (name "+3V3(A)") (class "Default")
      (node (ref "C60") (pin "2") (pinfunction "2_2") (pintype "passive"))
      (node (ref "C62") (pin "2") (pinfunction "2_2") (pintype "passive"))
      (node (ref "C67") (pin "1") (pinfunction "1_1") (pintype "passive"))
      (node (ref "FB2") (pin "P$2") (pinfunction "2_P$2") (pintype "passive"))
      (node (ref "IC16") (pin "22") (pinfunction "AVDD33_22") (pintype "power_in"))
      (node (ref "X5") (pin "3") (pinfunction "CT_3") (pintype "input"))
      (node (ref "X5") (pin "6") (pinfunction "CR_6") (pintype "input"))
    )
    (net (code "3") (name "+5V") (class "Default")
      (node (ref "C11") (pin "1") (pinfunction "+_1") (pintype "passive"))
      (node (ref "C12") (pin "1") (pinfunction "1_1") (pintype "passive"))
      (node (ref "C2") (pin "1") (pinfunction "1_1") (pintype "passive"))
      (node (ref "C45") (pin "1") (pinfunction "1_1") (pintype "passive"))
      (node (ref "C8") (pin "2") (pinfunction "2_2") (pintype "passive"))
      (node (ref "D1") (pin "C") (pinfunction "C_C") (pintype "passive"))
      (node (ref "IC1") (pin "6") (pinfunction "VCC_6") (pintype "passive"))
      (node (ref "IC3") (pin "8") (pinfunction "VSS_8") (pintype "passive"))
      (node (ref "IC5") (pin "3") (pinfunction "IN_3") (pintype "input"))
      (node (ref "IC9") (pin "5") (pinfunction "IN_5") (pintype "input"))
      (node (ref "JP6") (pin "NO") (pinfunction "NO_NO") (pintype "passive"))
      (node (ref "L1") (pin "1") (pinfunction "1_1") (pintype "passive"))
      (node (ref "R25") (pin "1") (pinfunction "1_1") (pintype "passive"))
      (node (ref "X1") (pin "35") (pinfunction "1_35") (pintype "passive"))
      (node (ref "X1") (pin "36") (pinfunction "1_36") (pintype "passive"))
      (node (ref "X2") (pin "5") (pinfunction "1_5") (pintype "passive"))
      (node (ref "X2") (pin "6") (pinfunction "1_6") (pintype "passive"))
    )
    (net (code "4") (name "+12V") (class "Default")
      (node (ref "X1") (pin "37") (pinfunction "1_37") (pintype "passive"))
      (node (ref "X1") (pin "38") (pinfunction "1_38") (pintype "passive"))
      (node (ref "X2") (pin "3") (pinfunction "1_3") (pintype "passive"))
      (node (ref "X2") (pin "4") (pinfunction "1_4") (pintype "passive"))
    )
    (net (code "5") (name "+VAUX") (class "Default")
      (node (ref "X1") (pin "5") (pinfunction "1_5") (pintype "passive"))
      (node (ref "X2") (pin "10") (pinfunction "1_10") (pintype "passive"))
    )
    (net (code "11") (name "BOOT0") (class "Default")
      (node (ref "IC4") (pin "166") (pinfunction "BOOT0_166") (pintype "input"))
      (node (ref "JP1") (pin "COM") (pinfunction "COM_COM") (pintype "passive"))
    )
    (net (code "12") (name "BYPASS_REG") (class "Default")
      (node (ref "IC4") (pin "48") (pinfunction "BYPASS_REG_48") (pintype "input"))
      (node (ref "R12") (pin "2") (pinfunction "2_2") (pintype "passive"))
    )
    (net (code "13") (name "DAC_OUT1") (class "Default")
      (node (ref "C53") (pin "2") (pinfunction "2_2") (pintype "passive"))
      (node (ref "IC4") (pin "50") (pinfunction "PA4_50") (pintype "bidirectional"))
    )
    (net (code "14") (name "DIN1") (class "Default")
      (node (ref "IC4") (pin "7") (pinfunction "PI8_7") (pintype "bidirectional"))
      (node (ref "R4") (pin "2") (pinfunction "2_2") (pintype "passive"))
    )
    (net (code "15") (name "DIN2") (class "Default")
      (node (ref "IC4") (pin "8") (pinfunction "PC13_8") (pintype "bidirectional"))
      (node (ref "R8") (pin "2") (pinfunction "2_2") (pintype "passive"))
    )
    (net (code "16") (name "DOUT1") (class "Default")
      (node (ref "IC3") (pin "2") (pinfunction "IN1_2") (pintype "input"))
      (node (ref "IC4") (pin "9") (pinfunction "PC14_9") (pintype "bidirectional"))
    )
    (net (code "17") (name "DOUT2") (class "Default")
      (node (ref "IC3") (pin "3") (pinfunction "IN2_3") (pintype "input"))
      (node (ref "IC4") (pin "10") (pinfunction "PC15_10") (pintype "bidirectional"))
    )
    (net (code "18") (name "ENC_A") (class "Default")
      (node (ref "C6") (pin "2") (pinfunction "2_2") (pintype "passive"))
      (node (ref "IC4") (pin "119") (pinfunction "PC6_119") (pintype "bidirectional"))
      (node (ref "R5") (pin "1") (pinfunction "1_1") (pintype "passive"))
    )
    (net (code "19") (name "ENC_B") (class "Default")
      (node (ref "C7") (pin "1") (pinfunction "1_1") (pintype "passive"))
      (node (ref "IC4") (pin "120") (pinfunction "PC7_120") (pintype "bidirectional"))
      (node (ref "R10") (pin "1") (pinfunction "1_1") (pintype "passive"))
    )
    (net (code "20") (name "ENC_SW") (class "Default")
      (node (ref "C3") (pin "2") (pinfunction "2_2") (pintype "passive"))
      (node (ref "IC4") (pin "173") (pinfunction "PI4_173") (pintype "bidirectional"))
      (node (ref "SW2") (pin "E") (pinfunction "2_E") (pintype "passive"))
    )
    (net (code "21") (name "ETH_COL") (class "Default")
      (node (ref "IC4") (pin "47") (pinfunction "PA3_47") (pintype "bidirectional"))
      (node (ref "RN2") (pin "2") (pinfunction "1_2") (pintype "passive"))
    )
    (net (code "22") (name "ETH_CRS") (class "Default")
      (node (ref "IC4") (pin "40") (pinfunction "PA0_40") (pintype "bidirectional"))
      (node (ref "JP7") (pin "1") (pinfunction "1_1") (pintype "passive"))
      (node (ref "RN1") (pin "4") (pinfunction "1_4") (pintype "passive"))
    )
    (net (code "23") (name "ETH_MDC") (class "Default")
      (node (ref "IC16") (pin "31") (pinfunction "MDC_31") (pintype "input"))
      (node (ref "IC4") (pin "33") (pinfunction "PC1_33") (pintype "bidirectional"))
    )
    (net (code "24") (name "ETH_MDIO") (class "Default")
      (node (ref "IC16") (pin "30") (pinfunction "MDIO_30") (pintype "bidirectional"))
      (node (ref "IC4") (pin "42") (pinfunction "PA2_42") (pintype "bidirectional"))
      (node (ref "R38") (pin "1") (pinfunction "1_1") (pintype "passive"))
    )
    (net (code "25") (name "ETH_RXD0") (class "Default")
      (node (ref "IC4") (pin "54") (pinfunction "PC4_54") (pintype "bidirectional"))
      (node (ref "RN2") (pin "3") (pinfunction "1_3") (pintype "passive"))
    )
    (net (code "26") (name "ETH_RXD1") (class "Default")
      (node (ref "IC4") (pin "55") (pinfunction "PC5_55") (pintype "bidirectional"))
      (node (ref "RN2") (pin "4") (pinfunction "1_4") (pintype "passive"))
    )
    (net (code "27") (name "ETH_RXD2") (class "Default")
      (node (ref "IC4") (pin "83") (pinfunction "PH6_83") (pintype "bidirectional"))
      (node (ref "RN3") (pin "1") (pinfunction "1_1") (pintype "passive"))
    )
    (net (code "28") (name "ETH_RXD3") (class "Default")
      (node (ref "IC4") (pin "84") (pinfunction "PH7_84") (pintype "bidirectional"))
      (node (ref "RN3") (pin "2") (pinfunction "1_2") (pintype "passive"))
    )
    (net (code "29") (name "ETH_RX_CLK") (class "Default")
      (node (ref "IC4") (pin "41") (pinfunction "PA1_41") (pintype "bidirectional"))
      (node (ref "RN1") (pin "2") (pinfunction "1_2") (pintype "passive"))
    )
    (net (code "30") (name "ETH_RX_DV") (class "Default")
      (node (ref "IC4") (pin "53") (pinfunction "PA7_53") (pintype "bidirectional"))
      (node (ref "RN1") (pin "3") (pinfunction "1_3") (pintype "passive"))
    )
    (net (code "31") (name "ETH_RX_ERR") (class "Default")
      (node (ref "IC4") (pin "79") (pinfunction "PB10_79") (pintype "bidirectional"))
      (node (ref "JP10") (pin "2") (pinfunction "2_2") (pintype "passive"))
    )
    (net (code "32") (name "ETH_TXD0") (class "Default")
      (node (ref "IC4") (pin "85") (pinfunction "PB12_85") (pintype "bidirectional"))
      (node (ref "RN4") (pin "1") (pinfunction "1_1") (pintype "passive"))
    )
    (net (code "33") (name "ETH_TXD1") (class "Default")
      (node (ref "IC4") (pin "86") (pinfunction "PB13_86") (pintype "bidirectional"))
      (node (ref "RN4") (pin "2") (pinfunction "1_2") (pintype "passive"))
    )
    (net (code "34") (name "ETH_TXD2") (class "Default")
      (node (ref "IC4") (pin "34") (pinfunction "PC2_34") (pintype "bidirectional"))
      (node (ref "RN4") (pin "3") (pinfunction "1_3") (pintype "passive"))
    )
    (net (code "35") (name "ETH_TXD3") (class "Default")
      (node (ref "IC4") (pin "167") (pinfunction "PB8_167") (pintype "bidirectional"))
      (node (ref "RN4") (pin "4") (pinfunction "1_4") (pintype "passive"))
    )
    (net (code "36") (name "ETH_TX_CLK") (class "Default")
      (node (ref "IC4") (pin "35") (pinfunction "PC3_35") (pintype "bidirectional"))
      (node (ref "RN3") (pin "3") (pinfunction "1_3") (pintype "passive"))
    )
    (net (code "37") (name "ETH_TX_EN") (class "Default")
      (node (ref "IC4") (pin "80") (pinfunction "PB11_80") (pintype "bidirectional"))
      (node (ref "RN3") (pin "4") (pinfunction "1_4") (pintype "passive"))
    )
    (net (code "38") (name "FMC_A0") (class "Default")
      (node (ref "IC4") (pin "16") (pinfunction "PF0_16") (pintype "bidirectional"))
      (node (ref "IC7") (pin "23") (pinfunction "A0_23") (pintype "input"))
    )
    (net (code "39") (name "FMC_A1") (class "Default")
      (node (ref "IC4") (pin "17") (pinfunction "PF1_17") (pintype "bidirectional"))
      (node (ref "IC7") (pin "24") (pinfunction "A1_24") (pintype "input"))
    )
    (net (code "40") (name "FMC_A2") (class "Default")
      (node (ref "IC4") (pin "18") (pinfunction "PF2_18") (pintype "bidirectional"))
      (node (ref "IC7") (pin "25") (pinfunction "A2_25") (pintype "input"))
    )
    (net (code "41") (name "FMC_A3") (class "Default")
      (node (ref "IC4") (pin "19") (pinfunction "PF3_19") (pintype "bidirectional"))
      (node (ref "IC7") (pin "26") (pinfunction "A3_26") (pintype "input"))
    )
    (net (code "42") (name "FMC_A4") (class "Default")
      (node (ref "IC4") (pin "20") (pinfunction "PF4_20") (pintype "bidirectional"))
      (node (ref "IC7") (pin "29") (pinfunction "A4_29") (pintype "input"))
    )
    (net (code "43") (name "FMC_A5") (class "Default")
      (node (ref "IC4") (pin "21") (pinfunction "PF5_21") (pintype "bidirectional"))
      (node (ref "IC7") (pin "30") (pinfunction "A5_30") (pintype "input"))
    )
    (net (code "44") (name "FMC_A6") (class "Default")
      (node (ref "IC4") (pin "60") (pinfunction "PF12_60") (pintype "bidirectional"))
      (node (ref "IC7") (pin "31") (pinfunction "A6_31") (pintype "input"))
    )
    (net (code "45") (name "FMC_A7") (class "Default")
      (node (ref "IC4") (pin "63") (pinfunction "PF13_63") (pintype "bidirectional"))
      (node (ref "IC7") (pin "32") (pinfunction "A7_32") (pintype "input"))
    )
    (net (code "46") (name "FMC_A8") (class "Default")
      (node (ref "IC4") (pin "64") (pinfunction "PF14_64") (pintype "bidirectional"))
      (node (ref "IC7") (pin "33") (pinfunction "A8_33") (pintype "input"))
    )
    (net (code "47") (name "FMC_A9") (class "Default")
      (node (ref "IC4") (pin "65") (pinfunction "PF15_65") (pintype "bidirectional"))
      (node (ref "IC7") (pin "34") (pinfunction "A9_34") (pintype "input"))
    )
    (net (code "48") (name "FMC_A10") (class "Default")
      (node (ref "IC4") (pin "66") (pinfunction "PG0_66") (pintype "bidirectional"))
      (node (ref "IC7") (pin "22") (pinfunction "A10/AP_22") (pintype "input"))
    )
    (net (code "49") (name "FMC_A11") (class "Default")
      (node (ref "IC4") (pin "67") (pinfunction "PG1_67") (pintype "bidirectional"))
      (node (ref "IC7") (pin "35") (pinfunction "A11_35") (pintype "input"))
    )
    (net (code "50") (name "FMC_BA0") (class "Default")
      (node (ref "IC4") (pin "112") (pinfunction "PG4_112") (pintype "bidirectional"))
      (node (ref "IC7") (pin "20") (pinfunction "BA0_20") (pintype "input"))
    )
    (net (code "51") (name "FMC_BA1") (class "Default")
      (node (ref "IC4") (pin "113") (pinfunction "PG5_113") (pintype "bidirectional"))
      (node (ref "IC7") (pin "21") (pinfunction "BA1_21") (pintype "input"))
    )
    (net (code "52") (name "FMC_D0") (class "Default")
      (node (ref "IC4") (pin "97") (pinfunction "PD14_97") (pintype "bidirectional"))
      (node (ref "IC7") (pin "2") (pinfunction "DQ0_2") (pintype "bidirectional"))
    )
    (net (code "53") (name "FMC_D1") (class "Default")
      (node (ref "IC4") (pin "98") (pinfunction "PD15_98") (pintype "bidirectional"))
      (node (ref "IC7") (pin "4") (pinfunction "DQ1_4") (pintype "bidirectional"))
    )
    (net (code "54") (name "FMC_D2") (class "Default")
      (node (ref "IC4") (pin "142") (pinfunction "PD0_142") (pintype "bidirectional"))
      (node (ref "IC7") (pin "5") (pinfunction "DQ2_5") (pintype "bidirectional"))
    )
    (net (code "55") (name "FMC_D3") (class "Default")
      (node (ref "IC4") (pin "143") (pinfunction "PD1_143") (pintype "bidirectional"))
      (node (ref "IC7") (pin "7") (pinfunction "DQ3_7") (pintype "bidirectional"))
    )
    (net (code "56") (name "FMC_D4") (class "Default")
      (node (ref "IC4") (pin "68") (pinfunction "PE7_68") (pintype "bidirectional"))
      (node (ref "IC7") (pin "8") (pinfunction "DQ4_8") (pintype "bidirectional"))
    )
    (net (code "57") (name "FMC_D5") (class "Default")
      (node (ref "IC4") (pin "69") (pinfunction "PE8_69") (pintype "bidirectional"))
      (node (ref "IC7") (pin "10") (pinfunction "DQ5_10") (pintype "bidirectional"))
    )
    (net (code "58") (name "FMC_D6") (class "Default")
      (node (ref "IC4") (pin "70") (pinfunction "PE9_70") (pintype "bidirectional"))
      (node (ref "IC7") (pin "11") (pinfunction "DQ6_11") (pintype "bidirectional"))
    )
    (net (code "59") (name "FMC_D7") (class "Default")
      (node (ref "IC4") (pin "73") (pinfunction "PE10_73") (pintype "bidirectional"))
      (node (ref "IC7") (pin "13") (pinfunction "DQ7_13") (pintype "bidirectional"))
    )
    (net (code "60") (name "FMC_D8") (class "Default")
      (node (ref "IC4") (pin "74") (pinfunction "PE11_74") (pintype "bidirectional"))
      (node (ref "IC7") (pin "42") (pinfunction "DQ8_42") (pintype "bidirectional"))
    )
    (net (code "61") (name "FMC_D9") (class "Default")
      (node (ref "IC4") (pin "75") (pinfunction "PE12_75") (pintype "bidirectional"))
      (node (ref "IC7") (pin "44") (pinfunction "DQ9_44") (pintype "bidirectional"))
    )
    (net (code "62") (name "FMC_D10") (class "Default")
      (node (ref "IC4") (pin "76") (pinfunction "PE13_76") (pintype "bidirectional"))
      (node (ref "IC7") (pin "45") (pinfunction "DQ10_45") (pintype "bidirectional"))
    )
    (net (code "63") (name "FMC_D11") (class "Default")
      (node (ref "IC4") (pin "77") (pinfunction "PE14_77") (pintype "bidirectional"))
      (node (ref "IC7") (pin "47") (pinfunction "DQ11_47") (pintype "bidirectional"))
    )
    (net (code "64") (name "FMC_D12") (class "Default")
      (node (ref "IC4") (pin "78") (pinfunction "PE15_78") (pintype "bidirectional"))
      (node (ref "IC7") (pin "48") (pinfunction "DQ12_48") (pintype "bidirectional"))
    )
    (net (code "65") (name "FMC_D13") (class "Default")
      (node (ref "IC4") (pin "89") (pinfunction "PD8_89") (pintype "bidirectional"))
      (node (ref "IC7") (pin "50") (pinfunction "DQ13_50") (pintype "bidirectional"))
    )
    (net (code "66") (name "FMC_D14") (class "Default")
      (node (ref "IC4") (pin "90") (pinfunction "PD9_90") (pintype "bidirectional"))
      (node (ref "IC7") (pin "51") (pinfunction "DQ14_51") (pintype "bidirectional"))
    )
    (net (code "67") (name "FMC_D15") (class "Default")
      (node (ref "IC4") (pin "91") (pinfunction "PD10_91") (pintype "bidirectional"))
      (node (ref "IC7") (pin "53") (pinfunction "DQ15_53") (pintype "bidirectional"))
    )
    (net (code "68") (name "FMC_NBL0") (class "Default")
      (node (ref "IC4") (pin "169") (pinfunction "PE0_169") (pintype "bidirectional"))
      (node (ref "IC7") (pin "15") (pinfunction "LDQM_15") (pintype "input"))
    )
    (net (code "69") (name "FMC_NBL1") (class "Default")
      (node (ref "IC4") (pin "170") (pinfunction "PE1_170") (pintype "bidirectional"))
      (node (ref "IC7") (pin "39") (pinfunction "UDQM_39") (pintype "input"))
    )
    (net (code "70") (name "FMC_SDCKE0") (class "Default")
      (node (ref "IC4") (pin "43") (pinfunction "PH2_43") (pintype "bidirectional"))
      (node (ref "IC7") (pin "37") (pinfunction "CKE_37") (pintype "input"))
    )
    (net (code "71") (name "FMC_SDCLK") (class "Default")
      (node (ref "IC4") (pin "116") (pinfunction "PG8_116") (pintype "bidirectional"))
      (node (ref "IC7") (pin "38") (pinfunction "CLK_38") (pintype "input"))
    )
    (net (code "72") (name "FMC_SDNCAS") (class "Default")
      (node (ref "IC4") (pin "160") (pinfunction "PG15_160") (pintype "bidirectional"))
      (node (ref "IC7") (pin "17") (pinfunction "~{CAS}_17") (pintype "input"))
    )
    (net (code "73") (name "FMC_SDNE0") (class "Default")
      (node (ref "IC4") (pin "44") (pinfunction "PH3_44") (pintype "bidirectional"))
      (node (ref "IC7") (pin "19") (pinfunction "~{CS}_19") (pintype "input"))
      (node (ref "R24") (pin "2") (pinfunction "2_2") (pintype "passive"))
    )
    (net (code "74") (name "FMC_SDNRAS") (class "Default")
      (node (ref "IC4") (pin "59") (pinfunction "PF11_59") (pintype "bidirectional"))
      (node (ref "IC7") (pin "18") (pinfunction "~{RAS}_18") (pintype "input"))
    )
    (net (code "75") (name "FMC_SDNWE") (class "Default")
      (node (ref "IC4") (pin "46") (pinfunction "PH5_46") (pintype "bidirectional"))
      (node (ref "IC7") (pin "16") (pinfunction "~{WE}_16") (pintype "input"))
    )
    (net (code "76") (name "GND") (class "Default")
      (node (ref "B1") (pin "2") (pinfunction "-_2") (pintype "passive"))
      (node (ref "C1") (pin "2") (pinfunction "2_2") (pintype "passive"))
      (node (ref "C10") (pin "1") (pinfunction "1_1") (pintype "passive"))
      (node (ref "C11") (pin "2") (pinfunction "-_2") (pintype "passive"))
      (node (ref "C12") (pin "2") (pinfunction "2_2") (pintype "passive"))
      (node (ref "C13") (pin "-") (pinfunction "-_-") (pintype "passive"))
      (node (ref "C14") (pin "2") (pinfunction "2_2") (pintype "passive"))
      (node (ref "C15") (pin "2") (pinfunction "2_2") (pintype "passive"))
      (node (ref "C16") (pin "2") (pinfunction "2_2") (pintype "passive"))
      (node (ref "C17") (pin "2") (pinfunction "2_2") (pintype "passive"))
      (node (ref "C18") (pin "2") (pinfunction "2_2") (pintype "passive"))
      (node (ref "C19") (pin "2") (pinfunction "2_2") (pintype "passive"))
      (node (ref "C2") (pin "2") (pinfunction "2_2") (pintype "passive"))
      (node (ref "C20") (pin "-") (pinfunction "-_-") (pintype "passive"))
      (node (ref "C21") (pin "2") (pinfunction "2_2") (pintype "passive"))
      (node (ref "C22") (pin "2") (pinfunction "2_2") (pintype "passive"))
      (node (ref "C23") (pin "2") (pinfunction "2_2") (pintype "passive"))
      (node (ref "C24") (pin "2") (pinfunction "2_2") (pintype "passive"))
      (node (ref "C25") (pin "2") (pinfunction "2_2") (pintype "passive"))
      (node (ref "C26") (pin "2") (pinfunction "2_2") (pintype "passive"))
      (node (ref "C27") (pin "2") (pinfunction "2_2") (pintype "passive"))
      (node (ref "C28") (pin "2") (pinfunction "2_2") (pintype "passive"))
      (node (ref "C29") (pin "2") (pinfunction "2_2") (pintype "passive"))
      (node (ref "C3") (pin "1") (pinfunction "1_1") (pintype "passive"))
      (node (ref "C30") (pin "2") (pinfunction "2_2") (pintype "passive"))
      (node (ref "C31") (pin "2") (pinfunction "2_2") (pintype "passive"))
      (node (ref "C32") (pin "2") (pinfunction "2_2") (pintype "passive"))
      (node (ref "C33") (pin "2") (pinfunction "2_2") (pintype "passive"))
      (node (ref "C34") (pin "2") (pinfunction "2_2") (pintype "passive"))
      (node (ref "C35") (pin "2") (pinfunction "2_2") (pintype "passive"))
      (node (ref "C36") (pin "2") (pinfunction "2_2") (pintype "passive"))
      (node (ref "C37") (pin "2") (pinfunction "2_2") (pintype "passive"))
      (node (ref "C38") (pin "1") (pinfunction "1_1") (pintype "passive"))
      (node (ref "C39") (pin "2") (pinfunction "2_2") (pintype "passive"))
      (node (ref "C4") (pin "1") (pinfunction "1_1") (pintype "passive"))
      (node (ref "C40") (pin "2") (pinfunction "2_2") (pintype "passive"))
      (node (ref "C41") (pin "2") (pinfunction "2_2") (pintype "passive"))
      (node (ref "C42") (pin "2") (pinfunction "2_2") (pintype "passive"))
      (node (ref "C43") (pin "2") (pinfunction "2_2") (pintype "passive"))
      (node (ref "C44") (pin "2") (pinfunction "2_2") (pintype "passive"))
      (node (ref "C45") (pin "2") (pinfunction "2_2") (pintype "passive"))
      (node (ref "C46") (pin "2") (pinfunction "2_2") (pintype "passive"))
      (node (ref "C47") (pin "-") (pinfunction "-_-") (pintype "passive"))
      (node (ref "C48") (pin "2") (pinfunction "2_2") (pintype "passive"))
      (node (ref "C49") (pin "2") (pinfunction "2_2") (pintype "passive"))
      (node (ref "C5") (pin "2") (pinfunction "2_2") (pintype "passive"))
      (node (ref "C50") (pin "1") (pinfunction "1_1") (pintype "passive"))
      (node (ref "C51") (pin "1") (pinfunction "1_1") (pintype "passive"))
      (node (ref "C52") (pin "2") (pinfunction "2_2") (pintype "passive"))
      (node (ref "C54") (pin "1") (pinfunction "1_1") (pintype "passive"))
      (node (ref "C55") (pin "1") (pinfunction "1_1") (pintype "passive"))
      (node (ref "C56") (pin "1") (pinfunction "1_1") (pintype "passive"))
      (node (ref "C57") (pin "1") (pinfunction "1_1") (pintype "passive"))
      (node (ref "C58") (pin "2") (pinfunction "2_2") (pintype "passive"))
      (node (ref "C59") (pin "2") (pinfunction "2_2") (pintype "passive"))
      (node (ref "C6") (pin "1") (pinfunction "1_1") (pintype "passive"))
      (node (ref "C60") (pin "1") (pinfunction "1_1") (pintype "passive"))
      (node (ref "C61") (pin "2") (pinfunction "2_2") (pintype "passive"))
      (node (ref "C62") (pin "1") (pinfunction "1_1") (pintype "passive"))
      (node (ref "C63") (pin "2") (pinfunction "2_2") (pintype "passive"))
      (node (ref "C64") (pin "2") (pinfunction "2_2") (pintype "passive"))
      (node (ref "C65") (pin "-") (pinfunction "-_-") (pintype "passive"))
      (node (ref "C66") (pin "2") (pinfunction "2_2") (pintype "passive"))
      (node (ref "C67") (pin "2") (pinfunction "2_2") (pintype "passive"))
      (node (ref "C68") (pin "2") (pinfunction "2_2") (pintype "passive"))
      (node (ref "C69") (pin "2") (pinfunction "2_2") (pintype "passive"))
      (node (ref "C7") (pin "2") (pinfunction "2_2") (pintype "passive"))
      (node (ref "C8") (pin "1") (pinfunction "1_1") (pintype "passive"))
      (node (ref "C9") (pin "1") (pinfunction "1_1") (pintype "passive"))
      (node (ref "D1") (pin "A") (pinfunction "A_A") (pintype "passive"))
      (node (ref "IC1") (pin "3") (pinfunction "GND_3") (pintype "power_in"))
      (node (ref "IC10") (pin "2") (pinfunction "GND_2") (pintype "power_in"))
      (node (ref "IC11") (pin "3") (pinfunction "GND_3") (pintype "power_in"))
      (node (ref "IC12") (pin "7") (pinfunction "GND_7") (pintype "passive"))
      (node (ref "IC12") (pin "TP") (pinfunction "TP_TP") (pintype "passive"))
      (node (ref "IC13") (pin "3") (pinfunction "GND_3") (pintype "power_in"))
      (node (ref "IC14") (pin "13") (pinfunction "A1_13") (pintype "input"))
      (node (ref "IC14") (pin "14") (pinfunction "A0_14") (pintype "input"))
      (node (ref "IC14") (pin "6") (pinfunction "GND_6") (pintype "passive"))
      (node (ref "IC15") (pin "3") (pinfunction "GND_3") (pintype "power_in"))
      (node (ref "IC16") (pin "15") (pinfunction "AGND-15_15") (pintype "power_in"))
      (node (ref "IC16") (pin "19") (pinfunction "AGND-19_19") (pintype "power_in"))
      (node (ref "IC16") (pin "35") (pinfunction "IOGND-35_35") (pintype "power_in"))
      (node (ref "IC16") (pin "36") (pinfunction "DGND_36") (pintype "power_in"))
      (node (ref "IC16") (pin "47") (pinfunction "IOGND-47_47") (pintype "power_in"))
      (node (ref "IC2") (pin "2") (pinfunction "VSS_2") (pintype "power_in"))
      (node (ref "IC3") (pin "6") (pinfunction "GND_6") (pintype "passive"))
      (node (ref "IC4") (pin "103") (pinfunction "VSSDSI_2_103") (pintype "power_in"))
      (node (ref "IC4") (pin "109") (pinfunction "VSSDSI_109") (pintype "power_in"))
      (node (ref "IC4") (pin "117") (pinfunction "VSS_7_117") (pintype "power_in"))
      (node (ref "IC4") (pin "130") (pinfunction "VSS_8_130") (pintype "power_in"))
      (node (ref "IC4") (pin "135") (pinfunction "VSS_9_135") (pintype "power_in"))
      (node (ref "IC4") (pin "14") (pinfunction "VSS_2_14") (pintype "power_in"))
      (node (ref "IC4") (pin "148") (pinfunction "VSS_10_148") (pintype "power_in"))
      (node (ref "IC4") (pin "158") (pinfunction "VSS_158") (pintype "power_in"))
      (node (ref "IC4") (pin "22") (pinfunction "VSS_3_22") (pintype "power_in"))
      (node (ref "IC4") (pin "37") (pinfunction "VSSA_37") (pintype "power_in"))
      (node (ref "IC4") (pin "61") (pinfunction "VSS_4_61") (pintype "power_in"))
      (node (ref "IC4") (pin "71") (pinfunction "VSS_5_71") (pintype "power_in"))
      (node (ref "IC4") (pin "95") (pinfunction "VSS_6_95") (pintype "power_in"))
      (node (ref "IC5") (pin "1") (pinfunction "ADJ_1") (pintype "input"))
      (node (ref "IC6") (pin "3") (pinfunction "GND_3") (pintype "power_in"))
      (node (ref "IC7") (pin "12") (pinfunction "GNDQ-12_12") (pintype "power_in"))
      (node (ref "IC7") (pin "28") (pinfunction "GND-28_28") (pintype "power_in"))
      (node (ref "IC7") (pin "41") (pinfunction "GND_41") (pintype "power_in"))
      (node (ref "IC7") (pin "46") (pinfunction "GNDQ-46_46") (pintype "power_in"))
      (node (ref "IC7") (pin "52") (pinfunction "GNDQ-52_52") (pintype "power_in"))
      (node (ref "IC7") (pin "54") (pinfunction "GND-54_54") (pintype "power_in"))
      (node (ref "IC7") (pin "6") (pinfunction "GNDQ-6_6") (pintype "power_in"))
      (node (ref "IC8") (pin "1") (pinfunction "A0_1") (pintype "input"))
      (node (ref "IC8") (pin "2") (pinfunction "A1_2") (pintype "input"))
      (node (ref "IC8") (pin "3") (pinfunction "A2_3") (pintype "input"))
      (node (ref "IC8") (pin "4") (pinfunction "GND_4") (pintype "passive"))
      (node (ref "IC8") (pin "7") (pinfunction "WP_7") (pintype "input"))
      (node (ref "IC9") (pin "2") (pinfunction "GND_2") (pintype "power_in"))
      (node (ref "J1") (pin "6") (pinfunction "VSS_6") (pintype "power_in"))
      (node (ref "J1") (pin "S") (pinfunction "SH_S") (pintype "passive"))
      (node (ref "J1") (pin "SW2") (pinfunction "SW2_SW2") (pintype "passive"))
      (node (ref "J2") (pin "5") (pinfunction "GND_5") (pintype "passive"))
      (node (ref "JP1") (pin "NC") (pinfunction "NC_NC") (pintype "passive"))
      (node (ref "JP4") (pin "NC") (pinfunction "NC_NC") (pintype "passive"))
      (node (ref "JP5") (pin "NC") (pinfunction "NC_NC") (pintype "passive"))
      (node (ref "LCD1") (pin "29") (pinfunction "GND-29_29") (pintype "power_in"))
      (node (ref "LCD1") (pin "3") (pinfunction "GND-3_3") (pintype "power_in"))
      (node (ref "Q1") (pin "E") (pinfunction "E_E") (pintype "passive"))
      (node (ref "R12") (pin "1") (pinfunction "1_1") (pintype "passive"))
      (node (ref "R19") (pin "1") (pinfunction "1_1") (pintype "passive"))
      (node (ref "R27") (pin "2") (pinfunction "2_2") (pintype "passive"))
      (node (ref "R41") (pin "1") (pinfunction "1_1") (pintype "passive"))
      (node (ref "R44") (pin "1") (pinfunction "1_1") (pintype "passive"))
      (node (ref "R54") (pin "1") (pinfunction "1_1") (pintype "passive"))
      (node (ref "SW1") (pin "2") (pinfunction "2_2") (pintype "passive"))
      (node (ref "SW2") (pin "C") (pinfunction "C_C") (pintype "passive"))
      (node (ref "SW2") (pin "D") (pinfunction "1_D") (pintype "passive"))
      (node (ref "SW2") (pin "GND1") (pinfunction "C_GND1") (pintype "passive"))
      (node (ref "SW2") (pin "GND2") (pinfunction "C_GND2") (pintype "passive"))
      (node (ref "TP1") (pin "1") (pinfunction "P$1_1") (pintype "bidirectional"))
      (node (ref "X1") (pin "1") (pinfunction "1_1") (pintype "passive"))
      (node (ref "X1") (pin "15") (pinfunction "1_15") (pintype "passive"))
      (node (ref "X1") (pin "16") (pinfunction "1_16") (pintype "passive"))
      (node (ref "X1") (pin "2") (pinfunction "1_2") (pintype "passive"))
      (node (ref "X1") (pin "29") (pinfunction "1_29") (pintype "passive"))
      (node (ref "X1") (pin "30") (pinfunction "1_30") (pintype "passive"))
      (node (ref "X1") (pin "34") (pinfunction "1_34") (pintype "passive"))
      (node (ref "X1") (pin "39") (pinfunction "1_39") (pintype "passive"))
      (node (ref "X1") (pin "40") (pinfunction "1_40") (pintype "passive"))
      (node (ref "X2") (pin "7") (pinfunction "1_7") (pintype "passive"))
      (node (ref "X2") (pin "8") (pinfunction "1_8") (pintype "passive"))
      (node (ref "X2") (pin "9") (pinfunction "1_9") (pintype "passive"))
      (node (ref "X3") (pin "3") (pinfunction "1_3") (pintype "passive"))
      (node (ref "X4") (pin "3") (pinfunction "S_3") (pintype "passive"))
      (node (ref "X5") (pin "4") (pinfunction "GND_4") (pintype "passive"))
      (node (ref "X5") (pin "5") (pinfunction "GND_5") (pintype "passive"))
      (node (ref "ZD1") (pin "A") (pinfunction "A_A") (pintype "passive"))
      (node (ref "ZD2") (pin "A") (pinfunction "A_A") (pintype "passive"))
    )
    (net (code "77") (name "I2C1_SCL") (class "Default")
      (node (ref "IC14") (pin "12") (pinfunction "SCL_12") (pintype "bidirectional"))
      (node (ref "IC4") (pin "164") (pinfunction "PB6_164") (pintype "bidirectional"))
      (node (ref "IC8") (pin "6") (pinfunction "SCL_6") (pintype "bidirectional"))
      (node (ref "R15") (pin "2") (pinfunction "2_2") (pintype "passive"))
      (node (ref "X1") (pin "12") (pinfunction "1_12") (pintype "passive"))
      (node (ref "X2") (pin "13") (pinfunction "1_13") (pintype "passive"))
    )
    (net (code "78") (name "I2C1_SDA") (class "Default")
      (node (ref "IC14") (pin "11") (pinfunction "SDA_11") (pintype "bidirectional"))
      (node (ref "IC4") (pin "165") (pinfunction "PB7_165") (pintype "bidirectional"))
      (node (ref "IC8") (pin "5") (pinfunction "SDA_5") (pintype "bidirectional"))
      (node (ref "R16") (pin "2") (pinfunction "2_2") (pintype "passive"))
      (node (ref "X1") (pin "14") (pinfunction "1_14") (pintype "passive"))
      (node (ref "X2") (pin "14") (pinfunction "1_14") (pintype "passive"))
    )
    (net (code "79") (name "IRQ_TOUCH") (class "Default")
      (node (ref "IC14") (pin "10") (pinfunction "~{PENIRQ}_10") (pintype "output"))
      (node (ref "IC4") (pin "151") (pinfunction "PD7_151") (pintype "bidirectional"))
    )
    (net (code "80") (name "LCD_DISP") (class "Default")
      (node (ref "LCD1") (pin "31") (pinfunction "DISP_31") (pintype "input"))
      (node (ref "R32") (pin "1") (pinfunction "1_1") (pintype "passive"))
    )
    (net (code "81") (name "LED_ACT") (class "Default")
      (node (ref "IC16") (pin "26") (pinfunction "AN_EN(LED_ACT/COL)_26") (pintype "output"))
      (node (ref "R42") (pin "2") (pinfunction "2_2") (pintype "passive"))
      (node (ref "R50") (pin "2") (pinfunction "2_2") (pintype "passive"))
    )
    (net (code "82") (name "LED_LINK") (class "Default")
      (node (ref "IC16") (pin "28") (pinfunction "AN_0(LED_LINK)_28") (pintype "output"))
      (node (ref "R49") (pin "2") (pinfunction "2_2") (pintype "passive"))
      (node (ref "R51") (pin "2") (pinfunction "2_2") (pintype "passive"))
    )
    (net (code "83") (name "LED_SPEED") (class "Default")
      (node (ref "IC16") (pin "27") (pinfunction "AN_1(LED_SPEED)_27") (pintype "output"))
      (node (ref "R47") (pin "2") (pinfunction "2_2") (pintype "passive"))
      (node (ref "SPEED") (pin "C") (pinfunction "C_C") (pintype "passive"))
    )
    (net (code "84") (name "LTDC_B2") (class "Default")
      (node (ref "IC4") (pin "150") (pinfunction "PD6_150") (pintype "bidirectional"))
      (node (ref "LCD1") (pin "23") (pinfunction "B2_23") (pintype "input"))
    )
    (net (code "85") (name "LTDC_B3") (class "Default")
      (node (ref "IC4") (pin "154") (pinfunction "PG11_154") (pintype "bidirectional"))
      (node (ref "LCD1") (pin "24") (pinfunction "B3_24") (pintype "input"))
    )
    (net (code "86") (name "LTDC_B4") (class "Default")
      (node (ref "IC4") (pin "155") (pinfunction "PG12_155") (pintype "bidirectional"))
      (node (ref "LCD1") (pin "25") (pinfunction "B4_25") (pintype "input"))
    )
    (net (code "87") (name "LTDC_B5") (class "Default")
      (node (ref "IC4") (pin "174") (pinfunction "PI5_174") (pintype "bidirectional"))
      (node (ref "LCD1") (pin "26") (pinfunction "B5_26") (pintype "input"))
    )
    (net (code "88") (name "LTDC_B6") (class "Default")
      (node (ref "IC4") (pin "175") (pinfunction "PI6_175") (pintype "bidirectional"))
      (node (ref "LCD1") (pin "27") (pinfunction "B6_27") (pintype "input"))
    )
    (net (code "89") (name "LTDC_B7") (class "Default")
      (node (ref "IC4") (pin "176") (pinfunction "PI7_176") (pintype "bidirectional"))
      (node (ref "LCD1") (pin "28") (pinfunction "B7_28") (pintype "input"))
    )
    (net (code "90") (name "LTDC_CLK") (class "Default")
      (node (ref "IC4") (pin "115") (pinfunction "PG7_115") (pintype "bidirectional"))
      (node (ref "LCD1") (pin "30") (pinfunction "CLK_30") (pintype "input"))
    )
    (net (code "91") (name "LTDC_DE") (class "Default")
      (node (ref "IC4") (pin "28") (pinfunction "PF10_28") (pintype "bidirectional"))
      (node (ref "LCD1") (pin "34") (pinfunction "DE/NC2_34") (pintype "passive"))
    )
    (net (code "92") (name "LTDC_G2") (class "Default")
      (node (ref "IC4") (pin "52") (pinfunction "PA6_52") (pintype "bidirectional"))
      (node (ref "LCD1") (pin "15") (pinfunction "G2_15") (pintype "input"))
    )
    (net (code "93") (name "LTDC_G3") (class "Default")
      (node (ref "IC4") (pin "153") (pinfunction "PG10_153") (pintype "bidirectional"))
      (node (ref "LCD1") (pin "16") (pinfunction "G3_16") (pintype "input"))
    )
    (net (code "94") (name "LTDC_G4") (class "Default")
      (node (ref "IC4") (pin "45") (pinfunction "PH4_45") (pintype "bidirectional"))
      (node (ref "LCD1") (pin "17") (pinfunction "G4_17") (pintype "input"))
    )
    (net (code "95") (name "LTDC_G5") (class "Default")
      (node (ref "IC4") (pin "132") (pinfunction "PI0_132") (pintype "bidirectional"))
      (node (ref "LCD1") (pin "18") (pinfunction "G5_18") (pintype "input"))
    )
    (net (code "96") (name "LTDC_G6") (class "Default")
      (node (ref "IC4") (pin "13") (pinfunction "PI11_13") (pintype "bidirectional"))
      (node (ref "LCD1") (pin "19") (pinfunction "G6_19") (pintype "input"))
    )
    (net (code "97") (name "LTDC_G7") (class "Default")
      (node (ref "IC4") (pin "145") (pinfunction "PD3_145") (pintype "bidirectional"))
      (node (ref "LCD1") (pin "20") (pinfunction "G7_20") (pintype "input"))
    )
    (net (code "98") (name "LTDC_HSYNC") (class "Default")
      (node (ref "IC4") (pin "12") (pinfunction "PI10_12") (pintype "bidirectional"))
      (node (ref "LCD1") (pin "32") (pinfunction "HSYNC_32") (pintype "input"))
    )
    (net (code "99") (name "LTDC_R2") (class "Default")
      (node (ref "IC4") (pin "139") (pinfunction "PC10_139") (pintype "bidirectional"))
      (node (ref "LCD1") (pin "7") (pinfunction "R2_7") (pintype "input"))
    )
    (net (code "100") (name "LTDC_R3") (class "Default")
      (node (ref "IC4") (pin "56") (pinfunction "PB0_56") (pintype "bidirectional"))
      (node (ref "LCD1") (pin "8") (pinfunction "R3_8") (pintype "input"))
    )
    (net (code "101") (name "LTDC_R4") (class "Default")
      (node (ref "IC4") (pin "51") (pinfunction "PA5_51") (pintype "bidirectional"))
      (node (ref "LCD1") (pin "9") (pinfunction "R4_9") (pintype "input"))
    )
    (net (code "102") (name "LTDC_R5") (class "Default")
      (node (ref "IC4") (pin "32") (pinfunction "PC0_32") (pintype "bidirectional"))
      (node (ref "LCD1") (pin "10") (pinfunction "R5_10") (pintype "input"))
    )
    (net (code "103") (name "LTDC_R6") (class "Default")
      (node (ref "IC4") (pin "57") (pinfunction "PB1_57") (pintype "bidirectional"))
      (node (ref "LCD1") (pin "11") (pinfunction "R6_11") (pintype "input"))
    )
    (net (code "104") (name "LTDC_R7") (class "Default")
      (node (ref "IC4") (pin "114") (pinfunction "PG6_114") (pintype "bidirectional"))
      (node (ref "LCD1") (pin "12") (pinfunction "R7_12") (pintype "input"))
    )
    (net (code "105") (name "LTDC_VSYNC") (class "Default")
      (node (ref "IC4") (pin "11") (pinfunction "PI9_11") (pintype "bidirectional"))
      (node (ref "LCD1") (pin "33") (pinfunction "VSYNC_33") (pintype "input"))
    )
    (net (code "106") (name "MCLK_25") (class "Default")
      (node (ref "IC4") (pin "122") (pinfunction "PC9_122") (pintype "bidirectional"))
      (node (ref "RN1") (pin "1") (pinfunction "1_1") (pintype "passive"))
    )
    (net (code "107") (name "Net-(B1-+-Pad1)") (class "Default")
      (node (ref "B1") (pin "1") (pinfunction "+_1") (pintype "passive"))
      (node (ref "B1") (pin "3") (pinfunction "+_3") (pintype "passive"))
      (node (ref "JP2") (pin "NC") (pinfunction "NC_NC") (pintype "passive"))
    )
    (net (code "108") (name "Net-(C52-Pad1)") (class "Default")
      (node (ref "C52") (pin "1") (pinfunction "1_1") (pintype "passive"))
      (node (ref "R34") (pin "2") (pinfunction "2_2") (pintype "passive"))
    )
    (net (code "109") (name "Net-(C53-Pad1)") (class "Default")
      (node (ref "C53") (pin "1") (pinfunction "1_1") (pintype "passive"))
      (node (ref "R35") (pin "2") (pinfunction "2_2") (pintype "passive"))
    )
    (net (code "110") (name "Net-(C59-Pad1)") (class "Default")
      (node (ref "C59") (pin "1") (pinfunction "1_1") (pintype "passive"))
      (node (ref "R39") (pin "1") (pinfunction "1_1") (pintype "passive"))
      (node (ref "R40") (pin "2") (pinfunction "2_2") (pintype "passive"))
    )
    (net (code "111") (name "Net-(C61-Pad1)") (class "Default")
      (node (ref "C61") (pin "1") (pinfunction "1_1") (pintype "passive"))
      (node (ref "R43") (pin "1") (pinfunction "1_1") (pintype "passive"))
      (node (ref "R48") (pin "2") (pinfunction "2_2") (pintype "passive"))
    )
    (net (code "112") (name "Net-(F1-P$1)") (class "Default")
      (node (ref "F1") (pin "1") (pinfunction "P$1_1") (pintype "bidirectional"))
      (node (ref "X3") (pin "4") (pinfunction "1_4") (pintype "passive"))
    )
    (net (code "113") (name "Net-(F1-P$2)") (class "Default")
      (node (ref "F1") (pin "2") (pinfunction "P$2_2") (pintype "bidirectional"))
      (node (ref "IC1") (pin "4") (pinfunction "IO3_4") (pintype "bidirectional"))
      (node (ref "IC3") (pin "7") (pinfunction "OUT1_7") (pintype "output"))
      (node (ref "ZD1") (pin "C") (pinfunction "C_C") (pintype "passive"))
    )
    (net (code "114") (name "Net-(F2-P$1)") (class "Default")
      (node (ref "F2") (pin "1") (pinfunction "P$1_1") (pintype "bidirectional"))
      (node (ref "X3") (pin "5") (pinfunction "1_5") (pintype "passive"))
    )
    (net (code "115") (name "Net-(F2-P$2)") (class "Default")
      (node (ref "F2") (pin "2") (pinfunction "P$2_2") (pintype "bidirectional"))
      (node (ref "IC1") (pin "5") (pinfunction "IO4_5") (pintype "bidirectional"))
      (node (ref "IC3") (pin "5") (pinfunction "OUT2_5") (pintype "output"))
      (node (ref "ZD2") (pin "C") (pinfunction "C_C") (pintype "passive"))
    )
    (net (code "116") (name "Net-(IC1-IO1)") (class "Default")
      (node (ref "IC1") (pin "1") (pinfunction "IO1_1") (pintype "bidirectional"))
      (node (ref "IC2") (pin "1") (pinfunction "I_1") (pintype "input"))
      (node (ref "R3") (pin "2") (pinfunction "2_2") (pintype "passive"))
    )
    (net (code "117") (name "Net-(IC1-IO2)") (class "Default")
      (node (ref "IC1") (pin "2") (pinfunction "IO2_2") (pintype "bidirectional"))
      (node (ref "IC2") (pin "3") (pinfunction "I_3") (pintype "input"))
      (node (ref "R7") (pin "2") (pinfunction "2_2") (pintype "passive"))
    )
    (net (code "118") (name "Net-(IC2A-O)") (class "Default")
      (node (ref "IC2") (pin "6") (pinfunction "O_6") (pintype "output"))
      (node (ref "R4") (pin "1") (pinfunction "1_1") (pintype "passive"))
    )
    (net (code "119") (name "Net-(IC2B-O)") (class "Default")
      (node (ref "IC2") (pin "4") (pinfunction "O_4") (pintype "output"))
      (node (ref "R8") (pin "1") (pinfunction "1_1") (pintype "passive"))
    )
    (net (code "120") (name "Net-(IC4D-VCAPDSI)") (class "Default")
      (node (ref "IC4") (pin "100") (pinfunction "VCAPDSI_100") (pintype "power_in"))
      (node (ref "IC4") (pin "106") (pinfunction "VDD12DSI_106") (pintype "power_in"))
    )
    (net (code "121") (name "Net-(IC10-SW)") (class "Default")
      (node (ref "D2") (pin "A") (pinfunction "A_A") (pintype "passive"))
      (node (ref "IC10") (pin "1") (pinfunction "SW_1") (pintype "output"))
      (node (ref "L1") (pin "2") (pinfunction "2_2") (pintype "passive"))
    )
    (net (code "122") (name "Net-(IC10-VIN)") (class "Default")
      (node (ref "IC10") (pin "5") (pinfunction "VIN_5") (pintype "input"))
      (node (ref "R25") (pin "2") (pinfunction "2_2") (pintype "passive"))
    )
    (net (code "123") (name "Net-(IC12-BYPASS)") (class "Default")
      (node (ref "C57") (pin "2") (pinfunction "2_2") (pintype "passive"))
      (node (ref "IC12") (pin "2") (pinfunction "BYPASS_2") (pintype "input"))
    )
    (net (code "124") (name "Net-(IC12-IN+)") (class "Default")
      (node (ref "IC12") (pin "3") (pinfunction "IN+_3") (pintype "input"))
      (node (ref "R33") (pin "2") (pinfunction "2_2") (pintype "passive"))
      (node (ref "R34") (pin "1") (pinfunction "1_1") (pintype "passive"))
    )
    (net (code "125") (name "Net-(IC12-IN-)") (class "Default")
      (node (ref "IC12") (pin "4") (pinfunction "IN-_4") (pintype "input"))
      (node (ref "R35") (pin "1") (pinfunction "1_1") (pintype "passive"))
      (node (ref "R37") (pin "2") (pinfunction "2_2") (pintype "passive"))
    )
    (net (code "126") (name "Net-(IC12-VDD)") (class "Default")
      (node (ref "C51") (pin "2") (pinfunction "2_2") (pintype "passive"))
      (node (ref "IC12") (pin "6") (pinfunction "VDD_6") (pintype "power_in"))
      (node (ref "JP6") (pin "COM") (pinfunction "COM_COM") (pintype "passive"))
    )
    (net (code "127") (name "Net-(IC12-VO+)") (class "Default")
      (node (ref "IC12") (pin "5") (pinfunction "VO+_5") (pintype "output"))
      (node (ref "R37") (pin "1") (pinfunction "1_1") (pintype "passive"))
      (node (ref "SP1") (pin "+") (pinfunction "+_+") (pintype "passive"))
    )
    (net (code "128") (name "Net-(IC12-VO-)") (class "Default")
      (node (ref "IC12") (pin "8") (pinfunction "VO-_8") (pintype "output"))
      (node (ref "R33") (pin "1") (pinfunction "1_1") (pintype "passive"))
      (node (ref "SP1") (pin "-") (pinfunction "-_-") (pintype "passive"))
    )
    (net (code "129") (name "Net-(IC12-~{SHDN})") (class "Default")
      (node (ref "IC12") (pin "1") (pinfunction "~{SHDN}_1") (pintype "input"))
      (node (ref "R36") (pin "1") (pinfunction "1_1") (pintype "passive"))
    )
    (net (code "130") (name "Net-(IC15-IO1)") (class "Default")
      (node (ref "IC15") (pin "1") (pinfunction "IO1_1") (pintype "bidirectional"))
      (node (ref "IC16") (pin "17") (pinfunction "TD+_17") (pintype "bidirectional"))
      (node (ref "R39") (pin "2") (pinfunction "2_2") (pintype "passive"))
      (node (ref "X5") (pin "1") (pinfunction "TD+_1") (pintype "input"))
    )
    (net (code "131") (name "Net-(IC15-IO2)") (class "Default")
      (node (ref "IC15") (pin "2") (pinfunction "IO2_2") (pintype "bidirectional"))
      (node (ref "IC16") (pin "16") (pinfunction "TD-_16") (pintype "bidirectional"))
      (node (ref "R40") (pin "1") (pinfunction "1_1") (pintype "passive"))
      (node (ref "X5") (pin "2") (pinfunction "TD-_2") (pintype "input"))
    )
    (net (code "132") (name "Net-(IC15-IO3)") (class "Default")
      (node (ref "IC15") (pin "4") (pinfunction "IO3_4") (pintype "bidirectional"))
      (node (ref "IC16") (pin "14") (pinfunction "RD+_14") (pintype "bidirectional"))
      (node (ref "R43") (pin "2") (pinfunction "2_2") (pintype "passive"))
      (node (ref "X5") (pin "7") (pinfunction "RD+_7") (pintype "input"))
    )
    (net (code "133") (name "Net-(IC15-IO4)") (class "Default")
      (node (ref "IC15") (pin "5") (pinfunction "IO4_5") (pintype "bidirectional"))
      (node (ref "IC16") (pin "13") (pinfunction "RD-_13") (pintype "bidirectional"))
      (node (ref "R48") (pin "1") (pinfunction "1_1") (pintype "passive"))
      (node (ref "X5") (pin "8") (pinfunction "RD-_8") (pintype "input"))
    )
    (net (code "134") (name "Net-(IC16-CRS{slash}CRS_DV{slash}LED_CFG)") (class "Default")
      (node (ref "IC16") (pin "40") (pinfunction "CRS/CRS_DV/LED_CFG_40") (pintype "output"))
      (node (ref "RN1") (pin "5") (pinfunction "2_5") (pintype "passive"))
    )
    (net (code "135") (name "Net-(IC16-MDIX_EN(RX_ER))") (class "Default")
      (node (ref "IC16") (pin "41") (pinfunction "MDIX_EN(RX_ER)_41") (pintype "output"))
      (node (ref "RN2") (pin "8") (pinfunction "2_8") (pintype "passive"))
    )
    (net (code "136") (name "Net-(IC16-MII_MODE(RX_DV))") (class "Default")
      (node (ref "IC16") (pin "39") (pinfunction "MII_MODE(RX_DV)_39") (pintype "output"))
      (node (ref "JP9") (pin "2") (pinfunction "2_2") (pintype "passive"))
      (node (ref "RN1") (pin "6") (pinfunction "2_6") (pintype "passive"))
    )
    (net (code "137") (name "Net-(IC16-PFBIN1)") (class "Default")
      (node (ref "C63") (pin "1") (pinfunction "1_1") (pintype "passive"))
      (node (ref "C64") (pin "1") (pinfunction "1_1") (pintype "passive"))
      (node (ref "C65") (pin "+") (pinfunction "+_+") (pintype "passive"))
      (node (ref "C66") (pin "1") (pinfunction "1_1") (pintype "passive"))
      (node (ref "IC16") (pin "18") (pinfunction "PFBIN1_18") (pintype "input"))
      (node (ref "IC16") (pin "23") (pinfunction "PFBOUT_23") (pintype "output"))
      (node (ref "IC16") (pin "37") (pinfunction "PFBIN2_37") (pintype "input"))
    )
    (net (code "138") (name "Net-(IC16-PHYAD0(COL))") (class "Default")
      (node (ref "IC16") (pin "42") (pinfunction "PHYAD0(COL)_42") (pintype "output"))
      (node (ref "RN2") (pin "7") (pinfunction "2_7") (pintype "passive"))
    )
    (net (code "139") (name "Net-(IC16-PHYAD1(RXD1_0))") (class "Default")
      (node (ref "IC16") (pin "43") (pinfunction "PHYAD1(RXD1_0)_43") (pintype "output"))
      (node (ref "RN2") (pin "6") (pinfunction "2_6") (pintype "passive"))
    )
    (net (code "140") (name "Net-(IC16-PHYAD2(RXD1_1))") (class "Default")
      (node (ref "IC16") (pin "44") (pinfunction "PHYAD2(RXD1_1)_44") (pintype "output"))
      (node (ref "RN2") (pin "5") (pinfunction "2_5") (pintype "passive"))
    )
    (net (code "141") (name "Net-(IC16-PHYAD3(RXD1_2))") (class "Default")
      (node (ref "IC16") (pin "45") (pinfunction "PHYAD3(RXD1_2)_45") (pintype "output"))
      (node (ref "RN3") (pin "8") (pinfunction "2_8") (pintype "passive"))
    )
    (net (code "142") (name "Net-(IC16-PHYAD4(RXD1_3))") (class "Default")
      (node (ref "IC16") (pin "46") (pinfunction "PHYAD4(RXD1_3)_46") (pintype "output"))
      (node (ref "RN3") (pin "7") (pinfunction "2_7") (pintype "passive"))
    )
    (net (code "143") (name "Net-(IC16-PWR_DOWN{slash}INT)") (class "Default")
      (node (ref "IC16") (pin "7") (pinfunction "PWR_DOWN/INT_7") (pintype "input"))
      (node (ref "JP11") (pin "2") (pinfunction "2_2") (pintype "passive"))
    )
    (net (code "144") (name "Net-(IC16-RBIAS)") (class "Default")
      (node (ref "IC16") (pin "24") (pinfunction "RBIAS_24") (pintype "input"))
      (node (ref "R54") (pin "2") (pinfunction "2_2") (pintype "passive"))
    )
    (net (code "145") (name "Net-(IC16-RESERVED-20)") (class "Default")
      (node (ref "IC16") (pin "20") (pinfunction "RESERVED-20_20") (pintype "bidirectional"))
      (node (ref "R53") (pin "2") (pinfunction "2_2") (pintype "passive"))
    )
    (net (code "146") (name "Net-(IC16-RESERVED-21)") (class "Default")
      (node (ref "IC16") (pin "21") (pinfunction "RESERVED-21_21") (pintype "bidirectional"))
      (node (ref "R52") (pin "2") (pinfunction "2_2") (pintype "passive"))
    )
    (net (code "147") (name "Net-(IC16-RX_CLK)") (class "Default")
      (node (ref "IC16") (pin "38") (pinfunction "RX_CLK_38") (pintype "output"))
      (node (ref "RN1") (pin "7") (pinfunction "2_7") (pintype "passive"))
    )
    (net (code "148") (name "Net-(IC16-TXD_0)") (class "Default")
      (node (ref "IC16") (pin "3") (pinfunction "TXD_0_3") (pintype "input"))
      (node (ref "RN4") (pin "8") (pinfunction "2_8") (pintype "passive"))
    )
    (net (code "149") (name "Net-(IC16-TXD_1)") (class "Default")
      (node (ref "IC16") (pin "4") (pinfunction "TXD_1_4") (pintype "input"))
      (node (ref "RN4") (pin "7") (pinfunction "2_7") (pintype "passive"))
    )
    (net (code "150") (name "Net-(IC16-TXD_2)") (class "Default")
      (node (ref "IC16") (pin "5") (pinfunction "TXD_2_5") (pintype "input"))
      (node (ref "RN4") (pin "6") (pinfunction "2_6") (pintype "passive"))
    )
    (net (code "151") (name "Net-(IC16-TXD_3{slash}SNI_MODE)") (class "Default")
      (node (ref "IC16") (pin "6") (pinfunction "TXD_3/SNI_MODE_6") (pintype "input"))
      (node (ref "RN4") (pin "5") (pinfunction "2_5") (pintype "passive"))
    )
    (net (code "152") (name "Net-(IC16-TX_CLK)") (class "Default")
      (node (ref "IC16") (pin "1") (pinfunction "TX_CLK_1") (pintype "output"))
      (node (ref "RN3") (pin "6") (pinfunction "2_6") (pintype "passive"))
    )
    (net (code "153") (name "Net-(IC16-TX_EN)") (class "Default")
      (node (ref "IC16") (pin "2") (pinfunction "TX_EN_2") (pintype "input"))
      (node (ref "RN3") (pin "5") (pinfunction "2_5") (pintype "passive"))
    )
    (net (code "154") (name "Net-(IC16-X1)") (class "Default")
      (node (ref "IC16") (pin "34") (pinfunction "X1_34") (pintype "input"))
      (node (ref "RN1") (pin "8") (pinfunction "2_8") (pintype "passive"))
    )
    (net (code "155") (name "Net-(JP7-Pad2)") (class "Default")
      (node (ref "JP7") (pin "2") (pinfunction "2_2") (pintype "passive"))
      (node (ref "R44") (pin "2") (pinfunction "2_2") (pintype "passive"))
    )
    (net (code "156") (name "Net-(JP8-Pad2)") (class "Default")
      (node (ref "JP8") (pin "2") (pinfunction "2_2") (pintype "passive"))
      (node (ref "R41") (pin "2") (pinfunction "2_2") (pintype "passive"))
    )
    (net (code "157") (name "Net-(JP9-Pad1)") (class "Default")
      (node (ref "JP9") (pin "1") (pinfunction "1_1") (pintype "passive"))
      (node (ref "R46") (pin "2") (pinfunction "2_2") (pintype "passive"))
    )
    (net (code "158") (name "Net-(JP10-Pad1)") (class "Default")
      (node (ref "JP10") (pin "1") (pinfunction "1_1") (pintype "passive"))
      (node (ref "JP8") (pin "1") (pinfunction "1_1") (pintype "passive"))
      (node (ref "RN2") (pin "1") (pinfunction "1_1") (pintype "passive"))
    )
    (net (code "159") (name "Net-(JP11-Pad1)") (class "Default")
      (node (ref "JP11") (pin "1") (pinfunction "1_1") (pintype "passive"))
      (node (ref "R55") (pin "2") (pinfunction "2_2") (pintype "passive"))
    )
    (net (code "160") (name "Net-(LCD1-B0)") (class "Default")
      (node (ref "JP4") (pin "COM") (pinfunction "COM_COM") (pintype "passive"))
      (node (ref "LCD1") (pin "13") (pinfunction "G0_13") (pintype "input"))
      (node (ref "LCD1") (pin "14") (pinfunction "G1_14") (pintype "input"))
      (node (ref "LCD1") (pin "21") (pinfunction "B0_21") (pintype "input"))
      (node (ref "LCD1") (pin "22") (pinfunction "B1_22") (pintype "input"))
      (node (ref "LCD1") (pin "5") (pinfunction "R0_5") (pintype "input"))
      (node (ref "LCD1") (pin "6") (pinfunction "R1_6") (pintype "input"))
    )
    (net (code "161") (name "Net-(LCD1-RESET)") (class "Default")
      (node (ref "JP5") (pin "COM") (pinfunction "COM_COM") (pintype "passive"))
      (node (ref "LCD1") (pin "36") (pinfunction "RESET_36") (pintype "input"))
    )
    (net (code "162") (name "Net-(Q1-PadB)") (class "Default")
      (node (ref "Q1") (pin "B") (pinfunction "B_B") (pintype "passive"))
      (node (ref "R29") (pin "2") (pinfunction "2_2") (pintype "passive"))
    )
    (net (code "163") (name "Net-(Q1-PadC)") (class "Default")
      (node (ref "Q1") (pin "C") (pinfunction "C_C") (pintype "passive"))
      (node (ref "R26") (pin "1") (pinfunction "1_1") (pintype "passive"))
    )
    (net (code "164") (name "Net-(R1-Pad2)") (class "Default")
      (node (ref "R1") (pin "2") (pinfunction "2_2") (pintype "passive"))
      (node (ref "R5") (pin "2") (pinfunction "2_2") (pintype "passive"))
      (node (ref "SW2") (pin "A") (pinfunction "A_A") (pintype "passive"))
    )
    (net (code "165") (name "Net-(R2-Pad1)") (class "Default")
      (node (ref "R2") (pin "1") (pinfunction "1_1") (pintype "passive"))
      (node (ref "X3") (pin "1") (pinfunction "1_1") (pintype "passive"))
    )
    (net (code "166") (name "Net-(R2-Pad2)") (class "Default")
      (node (ref "R2") (pin "2") (pinfunction "2_2") (pintype "passive"))
      (node (ref "R3") (pin "1") (pinfunction "1_1") (pintype "passive"))
    )
    (net (code "167") (name "Net-(R6-Pad2)") (class "Default")
      (node (ref "R6") (pin "2") (pinfunction "2_2") (pintype "passive"))
      (node (ref "R7") (pin "1") (pinfunction "1_1") (pintype "passive"))
    )
    (net (code "168") (name "Net-(R10-Pad2)") (class "Default")
      (node (ref "R10") (pin "2") (pinfunction "2_2") (pintype "passive"))
      (node (ref "R9") (pin "2") (pinfunction "2_2") (pintype "passive"))
      (node (ref "SW2") (pin "B") (pinfunction "B_B") (pintype "passive"))
    )
    (net (code "169") (name "Net-(R26-Pad2)") (class "Default")
      (node (ref "R26") (pin "2") (pinfunction "2_2") (pintype "passive"))
      (node (ref "VBUS") (pin "C") (pinfunction "C_C") (pintype "passive"))
    )
    (net (code "170") (name "Net-(R45-Pad2)") (class "Default")
      (node (ref "R45") (pin "2") (pinfunction "2_2") (pintype "passive"))
      (node (ref "SPEED") (pin "A") (pinfunction "A_A") (pintype "passive"))
    )
    (net (code "171") (name "Net-(X3B-1)") (class "Default")
      (node (ref "R6") (pin "1") (pinfunction "1_1") (pintype "passive"))
      (node (ref "X3") (pin "2") (pinfunction "1_2") (pintype "passive"))
    )
    (net (code "172") (name "Net-(X4A-S)") (class "Default")
      (node (ref "JP3") (pin "2") (pinfunction "2_2") (pintype "passive"))
      (node (ref "R19") (pin "2") (pinfunction "2_2") (pintype "passive"))
      (node (ref "X4") (pin "1") (pinfunction "S_1") (pintype "passive"))
    )
    (net (code "173") (name "Net-(X5-GREEN-C)") (class "Default")
      (node (ref "R51") (pin "1") (pinfunction "1_1") (pintype "passive"))
      (node (ref "X5") (pin "10") (pinfunction "GREEN-C_10") (pintype "passive"))
    )
    (net (code "174") (name "Net-(X5-YELLOW-C)") (class "Default")
      (node (ref "R50") (pin "1") (pinfunction "1_1") (pintype "passive"))
      (node (ref "X5") (pin "11") (pinfunction "YELLOW-C_11") (pintype "passive"))
    )
    (net (code "175") (name "OE_SYNC") (class "Default")
      (node (ref "IC4") (pin "94") (pinfunction "PD13_94") (pintype "bidirectional"))
      (node (ref "X1") (pin "10") (pinfunction "1_10") (pintype "passive"))
    )
    (net (code "176") (name "OUT_PAR") (class "Default")
      (node (ref "IC4") (pin "140") (pinfunction "PC11_140") (pintype "bidirectional"))
      (node (ref "X1") (pin "4") (pinfunction "1_4") (pintype "passive"))
    )
    (net (code "177") (name "OUT_SER") (class "Default")
      (node (ref "IC4") (pin "152") (pinfunction "PG9_152") (pintype "bidirectional"))
      (node (ref "X1") (pin "3") (pinfunction "1_3") (pintype "passive"))
    )
    (net (code "178") (name "PE") (class "Default")
      (node (ref "C1") (pin "1") (pinfunction "1_1") (pintype "passive"))
      (node (ref "C49") (pin "1") (pinfunction "1_1") (pintype "passive"))
      (node (ref "J2") (pin "SH1") (pinfunction "SH1_SH1") (pintype "bidirectional"))
      (node (ref "J2") (pin "SH1.1") (pinfunction "SH1_SH1.1") (pintype "bidirectional"))
      (node (ref "J2") (pin "SH2") (pinfunction "SH2_SH2") (pintype "bidirectional"))
      (node (ref "J2") (pin "SH2.2") (pinfunction "SH2_SH2.2") (pintype "bidirectional"))
      (node (ref "X2") (pin "1") (pinfunction "1_1") (pintype "passive"))
      (node (ref "X2") (pin "2") (pinfunction "1_2") (pintype "passive"))
      (node (ref "X5") (pin "SH") (pinfunction "SH_SH") (pintype "passive"))
      (node (ref "X5") (pin "SH2") (pinfunction "SH_SH2") (pintype "passive"))
    )
    (net (code "179") (name "PWR_DIRECT") (class "Default")
      (node (ref "IC4") (pin "110") (pinfunction "PG2_110") (pintype "bidirectional"))
      (node (ref "X2") (pin "12") (pinfunction "1_12") (pintype "passive"))
    )
    (net (code "180") (name "PWR_SSTART") (class "Default")
      (node (ref "IC4") (pin "111") (pinfunction "PG3_111") (pintype "bidirectional"))
      (node (ref "X2") (pin "11") (pinfunction "1_11") (pintype "passive"))
    )
    (net (code "181") (name "RCC_OSC_IN") (class "Default")
      (node (ref "C9") (pin "2") (pinfunction "2_2") (pintype "passive"))
      (node (ref "IC4") (pin "29") (pinfunction "PH0_29") (pintype "bidirectional"))
      (node (ref "R14") (pin "2") (pinfunction "2_2") (pintype "passive"))
      (node (ref "Y1") (pin "2") (pinfunction "2_2") (pintype "passive"))
    )
    (net (code "182") (name "RCC_OSC_OUT") (class "Default")
      (node (ref "C10") (pin "2") (pinfunction "2_2") (pintype "passive"))
      (node (ref "IC4") (pin "30") (pinfunction "PH1_30") (pintype "bidirectional"))
      (node (ref "R14") (pin "1") (pinfunction "1_1") (pintype "passive"))
      (node (ref "Y1") (pin "1") (pinfunction "1_1") (pintype "passive"))
    )
    (net (code "183") (name "SDMMC1_CK") (class "Default")
      (node (ref "IC4") (pin "141") (pinfunction "PC12_141") (pintype "bidirectional"))
      (node (ref "J1") (pin "5") (pinfunction "CLK_5") (pintype "passive"))
    )
    (net (code "184") (name "SDMMC1_CMD") (class "Default")
      (node (ref "IC4") (pin "144") (pinfunction "PD2_144") (pintype "bidirectional"))
      (node (ref "J1") (pin "3") (pinfunction "CMD_3") (pintype "passive"))
      (node (ref "R23") (pin "2") (pinfunction "2_2") (pintype "passive"))
    )
    (net (code "185") (name "SDMMC1_D0") (class "Default")
      (node (ref "IC4") (pin "121") (pinfunction "PC8_121") (pintype "bidirectional"))
      (node (ref "J1") (pin "7") (pinfunction "DAT0_7") (pintype "passive"))
      (node (ref "R22") (pin "2") (pinfunction "2_2") (pintype "passive"))
    )
    (net (code "186") (name "SD_DETECT") (class "Default")
      (node (ref "IC4") (pin "24") (pinfunction "PF6_24") (pintype "bidirectional"))
      (node (ref "J1") (pin "SW1") (pinfunction "SW1_SW1") (pintype "passive"))
    )
    (net (code "187") (name "SPI2_CLK") (class "Default")
      (node (ref "IC4") (pin "133") (pinfunction "PI1_133") (pintype "bidirectional"))
      (node (ref "X1") (pin "32") (pinfunction "1_32") (pintype "passive"))
    )
    (net (code "188") (name "SPI2_CSA") (class "Default")
      (node (ref "IC4") (pin "93") (pinfunction "PD12_93") (pintype "bidirectional"))
      (node (ref "X1") (pin "28") (pinfunction "1_28") (pintype "passive"))
    )
    (net (code "189") (name "SPI2_CSB") (class "Default")
      (node (ref "IC4") (pin "92") (pinfunction "PD11_92") (pintype "bidirectional"))
      (node (ref "X1") (pin "27") (pinfunction "1_27") (pintype "passive"))
    )
    (net (code "190") (name "SPI2_IRQ") (class "Default")
      (node (ref "IC4") (pin "123") (pinfunction "PA8_123") (pintype "bidirectional"))
      (node (ref "X1") (pin "25") (pinfunction "1_25") (pintype "passive"))
    )
    (net (code "191") (name "SPI2_MISO") (class "Default")
      (node (ref "IC4") (pin "87") (pinfunction "PB14_87") (pintype "bidirectional"))
      (node (ref "X1") (pin "31") (pinfunction "1_31") (pintype "passive"))
    )
    (net (code "192") (name "SPI2_MOSI") (class "Default")
      (node (ref "IC4") (pin "134") (pinfunction "PI3_134") (pintype "bidirectional"))
      (node (ref "X1") (pin "33") (pinfunction "1_33") (pintype "passive"))
    )
    (net (code "193") (name "SPI4_CLK") (class "Default")
      (node (ref "IC4") (pin "1") (pinfunction "PE2_1") (pintype "bidirectional"))
      (node (ref "X1") (pin "23") (pinfunction "1_23") (pintype "passive"))
    )
    (net (code "194") (name "SPI4_CSA") (class "Default")
      (node (ref "IC4") (pin "2") (pinfunction "PE3_2") (pintype "bidirectional"))
      (node (ref "X1") (pin "22") (pinfunction "1_22") (pintype "passive"))
    )
    (net (code "195") (name "SPI4_CSB") (class "Default")
      (node (ref "IC4") (pin "3") (pinfunction "PE4_3") (pintype "bidirectional"))
      (node (ref "X1") (pin "21") (pinfunction "1_21") (pintype "passive"))
    )
    (net (code "196") (name "SPI4_IRQ") (class "Default")
      (node (ref "IC4") (pin "168") (pinfunction "PB9_168") (pintype "bidirectional"))
      (node (ref "X1") (pin "19") (pinfunction "1_19") (pintype "passive"))
    )
    (net (code "197") (name "SPI4_MISO") (class "Default")
      (node (ref "IC4") (pin "4") (pinfunction "PE5_4") (pintype "bidirectional"))
      (node (ref "X1") (pin "24") (pinfunction "1_24") (pintype "passive"))
    )
    (net (code "198") (name "SPI4_MOSI") (class "Default")
      (node (ref "IC4") (pin "5") (pinfunction "PE6_5") (pintype "bidirectional"))
      (node (ref "X1") (pin "26") (pinfunction "1_26") (pintype "passive"))
    )
    (net (code "199") (name "SPI5_CLK") (class "Default")
      (node (ref "IC4") (pin "25") (pinfunction "PF7_25") (pintype "bidirectional"))
      (node (ref "X1") (pin "17") (pinfunction "1_17") (pintype "passive"))
    )
    (net (code "200") (name "SPI5_CSA") (class "Default")
      (node (ref "IC4") (pin "157") (pinfunction "PG14_157") (pintype "bidirectional"))
      (node (ref "X1") (pin "11") (pinfunction "1_11") (pintype "passive"))
    )
    (net (code "201") (name "SPI5_CSB") (class "Default")
      (node (ref "IC4") (pin "156") (pinfunction "PG13_156") (pintype "bidirectional"))
      (node (ref "X1") (pin "13") (pinfunction "1_13") (pintype "passive"))
    )
    (net (code "202") (name "SPI5_IRQ") (class "Default")
      (node (ref "IC4") (pin "138") (pinfunction "PA15_138") (pintype "bidirectional"))
      (node (ref "X1") (pin "9") (pinfunction "1_9") (pintype "passive"))
    )
    (net (code "203") (name "SPI5_MISO") (class "Default")
      (node (ref "IC4") (pin "26") (pinfunction "PF8_26") (pintype "bidirectional"))
      (node (ref "X1") (pin "18") (pinfunction "1_18") (pintype "passive"))
    )
    (net (code "204") (name "SPI5_MOSI") (class "Default")
      (node (ref "IC4") (pin "27") (pinfunction "PF9_27") (pintype "bidirectional"))
      (node (ref "X1") (pin "20") (pinfunction "1_20") (pintype "passive"))
    )
    (net (code "205") (name "SYS_JTCK-SWCLK") (class "Default")
      (node (ref "IC4") (pin "137") (pinfunction "PA14_137") (pintype "bidirectional"))
      (node (ref "R21") (pin "1") (pinfunction "1_1") (pintype "passive"))
    )
    (net (code "206") (name "SYS_JTDO-SWO") (class "Default")
      (node (ref "IC4") (pin "161") (pinfunction "PB3_161") (pintype "bidirectional"))
      (node (ref "IC6") (pin "5") (pinfunction "IO4_5") (pintype "bidirectional"))
      (node (ref "X4") (pin "6") (pinfunction "S_6") (pintype "passive"))
    )
    (net (code "207") (name "SYS_JTMS-SWDIO") (class "Default")
      (node (ref "IC4") (pin "128") (pinfunction "PA13_128") (pintype "bidirectional"))
      (node (ref "R20") (pin "1") (pinfunction "1_1") (pintype "passive"))
    )
    (net (code "208") (name "TCK") (class "Default")
      (node (ref "IC6") (pin "1") (pinfunction "IO1_1") (pintype "bidirectional"))
      (node (ref "R21") (pin "2") (pinfunction "2_2") (pintype "passive"))
      (node (ref "X4") (pin "2") (pinfunction "S_2") (pintype "passive"))
    )
    (net (code "209") (name "TFT_BRIGHTNESS") (class "Default")
      (node (ref "IC10") (pin "4") (pinfunction "CTRL_4") (pintype "input"))
      (node (ref "IC4") (pin "88") (pinfunction "PB15_88") (pintype "bidirectional"))
    )
    (net (code "210") (name "TMS") (class "Default")
      (node (ref "IC6") (pin "2") (pinfunction "IO2_2") (pintype "bidirectional"))
      (node (ref "R20") (pin "2") (pinfunction "2_2") (pintype "passive"))
      (node (ref "X4") (pin "4") (pinfunction "S_4") (pintype "passive"))
    )
    (net (code "211") (name "USB_D_N") (class "Default")
      (node (ref "IC11") (pin "1") (pinfunction "IO1_1") (pintype "bidirectional"))
      (node (ref "J2") (pin "2") (pinfunction "D-_2") (pintype "passive"))
      (node (ref "R30") (pin "1") (pinfunction "1_1") (pintype "passive"))
    )
    (net (code "212") (name "USB_D_P") (class "Default")
      (node (ref "IC11") (pin "2") (pinfunction "IO2_2") (pintype "bidirectional"))
      (node (ref "J2") (pin "3") (pinfunction "D+_3") (pintype "passive"))
      (node (ref "R31") (pin "1") (pinfunction "1_1") (pintype "passive"))
    )
    (net (code "213") (name "USB_OTG_FS_D_N") (class "Default")
      (node (ref "IC4") (pin "126") (pinfunction "PA11_126") (pintype "bidirectional"))
      (node (ref "R30") (pin "2") (pinfunction "2_2") (pintype "passive"))
    )
    (net (code "214") (name "USB_OTG_FS_D_P") (class "Default")
      (node (ref "IC4") (pin "127") (pinfunction "PA12_127") (pintype "bidirectional"))
      (node (ref "R31") (pin "2") (pinfunction "2_2") (pintype "passive"))
    )
    (net (code "215") (name "USB_OTG_FS_ID") (class "Default")
      (node (ref "IC11") (pin "4") (pinfunction "IO3_4") (pintype "bidirectional"))
      (node (ref "IC4") (pin "125") (pinfunction "PA10_125") (pintype "bidirectional"))
      (node (ref "J2") (pin "4") (pinfunction "ID_4") (pintype "passive"))
    )
    (net (code "216") (name "USB_OTG_FS_PSO") (class "Default")
      (node (ref "IC4") (pin "147") (pinfunction "PD5_147") (pintype "bidirectional"))
      (node (ref "IC9") (pin "4") (pinfunction "EN_4") (pintype "input"))
    )
    (net (code "217") (name "USB_OTG_FS_VBUS") (class "Default")
      (node (ref "C47") (pin "+") (pinfunction "+_+") (pintype "passive"))
      (node (ref "C50") (pin "2") (pinfunction "2_2") (pintype "passive"))
      (node (ref "IC11") (pin "6") (pinfunction "VCC_6") (pintype "passive"))
      (node (ref "IC4") (pin "124") (pinfunction "PA9_124") (pintype "bidirectional"))
      (node (ref "IC9") (pin "1") (pinfunction "OUT_1") (pintype "output"))
      (node (ref "J2") (pin "1") (pinfunction "VCC_1") (pintype "passive"))
      (node (ref "R29") (pin "1") (pinfunction "1_1") (pintype "passive"))
    )
    (net (code "218") (name "USER_SW") (class "Default")
      (node (ref "C4") (pin "2") (pinfunction "2_2") (pintype "passive"))
      (node (ref "IC4") (pin "163") (pinfunction "PB5_163") (pintype "bidirectional"))
      (node (ref "SW1") (pin "1") (pinfunction "1_1") (pintype "passive"))
    )
    (net (code "219") (name "VBAT") (class "Default")
      (node (ref "IC4") (pin "6") (pinfunction "VBAT_6") (pintype "power_in"))
      (node (ref "JP2") (pin "COM") (pinfunction "COM_COM") (pintype "passive"))
    )
    (net (code "220") (name "VCAP1") (class "Default")
      (node (ref "C35") (pin "1") (pinfunction "1_1") (pintype "passive"))
      (node (ref "IC4") (pin "81") (pinfunction "VCAP_1_81") (pintype "power_in"))
    )
    (net (code "221") (name "VCAP2") (class "Default")
      (node (ref "C34") (pin "1") (pinfunction "1_1") (pintype "passive"))
      (node (ref "IC4") (pin "129") (pinfunction "VCAP_2_129") (pintype "power_in"))
    )
    (net (code "222") (name "VDD") (class "Default")
      (node (ref "C14") (pin "1") (pinfunction "1_1") (pintype "passive"))
      (node (ref "C15") (pin "1") (pinfunction "1_1") (pintype "passive"))
      (node (ref "C16") (pin "1") (pinfunction "1_1") (pintype "passive"))
      (node (ref "C17") (pin "1") (pinfunction "1_1") (pintype "passive"))
      (node (ref "C18") (pin "1") (pinfunction "1_1") (pintype "passive"))
      (node (ref "C19") (pin "1") (pinfunction "1_1") (pintype "passive"))
      (node (ref "C20") (pin "+") (pinfunction "+_+") (pintype "passive"))
      (node (ref "C21") (pin "1") (pinfunction "1_1") (pintype "passive"))
      (node (ref "C22") (pin "1") (pinfunction "1_1") (pintype "passive"))
      (node (ref "C23") (pin "1") (pinfunction "1_1") (pintype "passive"))
      (node (ref "C24") (pin "1") (pinfunction "1_1") (pintype "passive"))
      (node (ref "C25") (pin "1") (pinfunction "1_1") (pintype "passive"))
      (node (ref "C26") (pin "1") (pinfunction "1_1") (pintype "passive"))
      (node (ref "C27") (pin "1") (pinfunction "1_1") (pintype "passive"))
      (node (ref "C28") (pin "1") (pinfunction "1_1") (pintype "passive"))
      (node (ref "C29") (pin "1") (pinfunction "1_1") (pintype "passive"))
      (node (ref "C30") (pin "1") (pinfunction "1_1") (pintype "passive"))
      (node (ref "C31") (pin "1") (pinfunction "1_1") (pintype "passive"))
      (node (ref "FB1") (pin "P$1") (pinfunction "1_P$1") (pintype "passive"))
      (node (ref "IC4") (pin "118") (pinfunction "VDDUSB_118") (pintype "power_in"))
      (node (ref "IC4") (pin "131") (pinfunction "VDD_10_131") (pintype "power_in"))
      (node (ref "IC4") (pin "136") (pinfunction "VDD_11_136") (pintype "power_in"))
      (node (ref "IC4") (pin "149") (pinfunction "VDDSDMMC_149") (pintype "power_in"))
      (node (ref "IC4") (pin "15") (pinfunction "VDD_2_15") (pintype "power_in"))
      (node (ref "IC4") (pin "159") (pinfunction "VDD_12_159") (pintype "power_in"))
      (node (ref "IC4") (pin "171") (pinfunction "PDR_ON_171") (pintype "passive"))
      (node (ref "IC4") (pin "172") (pinfunction "VDD_172") (pintype "power_in"))
      (node (ref "IC4") (pin "23") (pinfunction "VDD_3_23") (pintype "power_in"))
      (node (ref "IC4") (pin "36") (pinfunction "VDD_4_36") (pintype "power_in"))
      (node (ref "IC4") (pin "49") (pinfunction "VDD_5_49") (pintype "power_in"))
      (node (ref "IC4") (pin "62") (pinfunction "VDD_6_62") (pintype "power_in"))
      (node (ref "IC4") (pin "72") (pinfunction "VDD_7_72") (pintype "power_in"))
      (node (ref "IC4") (pin "82") (pinfunction "VDD_8_82") (pintype "power_in"))
      (node (ref "IC4") (pin "96") (pinfunction "VDD_9_96") (pintype "power_in"))
      (node (ref "IC4") (pin "99") (pinfunction "VDDDSI_99") (pintype "power_in"))
      (node (ref "JP1") (pin "NO") (pinfunction "NO_NO") (pintype "passive"))
      (node (ref "JP2") (pin "NO") (pinfunction "NO_NO") (pintype "passive"))
      (node (ref "R11") (pin "1") (pinfunction "1_1") (pintype "passive"))
      (node (ref "R17") (pin "2") (pinfunction "2_2") (pintype "passive"))
    )
    (net (code "223") (name "VDDA") (class "Default")
      (node (ref "C32") (pin "1") (pinfunction "1_1") (pintype "passive"))
      (node (ref "C33") (pin "1") (pinfunction "1_1") (pintype "passive"))
      (node (ref "FB1") (pin "P$2") (pinfunction "2_P$2") (pintype "passive"))
      (node (ref "IC4") (pin "39") (pinfunction "VDDA_39") (pintype "power_in"))
      (node (ref "R18") (pin "2") (pinfunction "2_2") (pintype "passive"))
    )
    (net (code "224") (name "VLED+") (class "Default")
      (node (ref "C46") (pin "1") (pinfunction "1_1") (pintype "passive"))
      (node (ref "D2") (pin "C") (pinfunction "C_C") (pintype "passive"))
      (node (ref "LCD1") (pin "2") (pinfunction "VLED+_2") (pintype "power_in"))
      (node (ref "ZD3") (pin "C") (pinfunction "C_C") (pintype "passive"))
    )
    (net (code "225") (name "VLED-") (class "Default")
      (node (ref "IC10") (pin "3") (pinfunction "FB_3") (pintype "input"))
      (node (ref "LCD1") (pin "1") (pinfunction "VLED-_1") (pintype "power_in"))
      (node (ref "R27") (pin "1") (pinfunction "1_1") (pintype "passive"))
      (node (ref "ZD3") (pin "A") (pinfunction "A_A") (pintype "passive"))
    )
    (net (code "226") (name "VREF+") (class "Default")
      (node (ref "IC4") (pin "38") (pinfunction "VREF+_38") (pintype "power_in"))
      (node (ref "R18") (pin "1") (pinfunction "1_1") (pintype "passive"))
    )
    (net (code "227") (name "XL") (class "Default")
      (node (ref "IC13") (pin "4") (pinfunction "IO3_4") (pintype "bidirectional"))
      (node (ref "IC14") (pin "4") (pinfunction "X-_4") (pintype "input"))
      (node (ref "LCD1") (pin "39") (pinfunction "XL_39") (pintype "passive"))
    )
    (net (code "228") (name "XR") (class "Default")
      (node (ref "IC13") (pin "1") (pinfunction "IO1_1") (pintype "bidirectional"))
      (node (ref "IC14") (pin "2") (pinfunction "X+_2") (pintype "input"))
      (node (ref "LCD1") (pin "37") (pinfunction "XR_37") (pintype "passive"))
    )
    (net (code "229") (name "YD") (class "Default")
      (node (ref "IC13") (pin "2") (pinfunction "IO2_2") (pintype "bidirectional"))
      (node (ref "IC14") (pin "5") (pinfunction "Y-_5") (pintype "input"))
      (node (ref "LCD1") (pin "38") (pinfunction "YD_38") (pintype "passive"))
    )
    (net (code "230") (name "YU") (class "Default")
      (node (ref "IC13") (pin "5") (pinfunction "IO4_5") (pintype "bidirectional"))
      (node (ref "IC14") (pin "3") (pinfunction "Y+_3") (pintype "input"))
      (node (ref "LCD1") (pin "40") (pinfunction "YU_40") (pintype "passive"))
    )
    (net (code "231") (name "unconnected-(IC4A-PB4-Pad162)") (class "Default")
      (node (ref "IC4") (pin "162") (pinfunction "PB4_162") (pintype "bidirectional"))
    )
    (net (code "232") (name "unconnected-(IC4C-DSI_CKN-Pad105)") (class "Default")
      (node (ref "IC4") (pin "105") (pinfunction "DSI_CKN_105") (pintype "bidirectional"))
    )
    (net (code "233") (name "unconnected-(IC4C-DSI_CKP-Pad104)") (class "Default")
      (node (ref "IC4") (pin "104") (pinfunction "DSI_CKP_104") (pintype "bidirectional"))
    )
    (net (code "234") (name "unconnected-(IC4C-DSI_D0N-Pad102)") (class "Default")
      (node (ref "IC4") (pin "102") (pinfunction "DSI_D0N_102") (pintype "bidirectional"))
    )
    (net (code "235") (name "unconnected-(IC4C-DSI_D0P-Pad101)") (class "Default")
      (node (ref "IC4") (pin "101") (pinfunction "DSI_D0P_101") (pintype "bidirectional"))
    )
    (net (code "236") (name "unconnected-(IC4C-DSI_D1N-Pad108)") (class "Default")
      (node (ref "IC4") (pin "108") (pinfunction "DSI_D1N_108") (pintype "bidirectional"))
    )
    (net (code "237") (name "unconnected-(IC4C-DSI_D1P-Pad107)") (class "Default")
      (node (ref "IC4") (pin "107") (pinfunction "DSI_D1P_107") (pintype "bidirectional"))
    )
    (net (code "238") (name "unconnected-(IC7-A12{slash}NC-36-Pad36)") (class "Default")
      (node (ref "IC7") (pin "36") (pinfunction "A12/NC-36_36") (pintype "passive"))
    )
    (net (code "239") (name "unconnected-(IC7-NC-40-Pad40)") (class "Default")
      (node (ref "IC7") (pin "40") (pinfunction "NC-40_40") (pintype "no_connect"))
    )
    (net (code "240") (name "unconnected-(IC11-IO4-Pad5)") (class "Default")
      (node (ref "IC11") (pin "5") (pinfunction "IO4_5") (pintype "bidirectional"))
    )
    (net (code "241") (name "unconnected-(IC14-AUX-Pad16)") (class "Default")
      (node (ref "IC14") (pin "16") (pinfunction "AUX_16") (pintype "input"))
    )
    (net (code "242") (name "unconnected-(IC16-CLK_OUT-Pad25)") (class "Default")
      (node (ref "IC16") (pin "25") (pinfunction "CLK_OUT_25") (pintype "output"))
    )
    (net (code "243") (name "unconnected-(IC16-TCK-Pad8)") (class "Default")
      (node (ref "IC16") (pin "8") (pinfunction "TCK_8") (pintype "input"))
    )
    (net (code "244") (name "unconnected-(IC16-TDI-Pad12)") (class "Default")
      (node (ref "IC16") (pin "12") (pinfunction "TDI_12") (pintype "input"))
    )
    (net (code "245") (name "unconnected-(IC16-TDO-Pad9)") (class "Default")
      (node (ref "IC16") (pin "9") (pinfunction "TDO_9") (pintype "output"))
    )
    (net (code "246") (name "unconnected-(IC16-TMS-Pad10)") (class "Default")
      (node (ref "IC16") (pin "10") (pinfunction "TMS_10") (pintype "input"))
    )
    (net (code "247") (name "unconnected-(IC16-X2-Pad33)") (class "Default")
      (node (ref "IC16") (pin "33") (pinfunction "X2_33") (pintype "output"))
    )
    (net (code "248") (name "unconnected-(IC16-~{TRST}-Pad11)") (class "Default")
      (node (ref "IC16") (pin "11") (pinfunction "~{TRST}_11") (pintype "input"))
    )
    (net (code "249") (name "unconnected-(J1-CD{slash}DAT3-Pad2)") (class "Default")
      (node (ref "J1") (pin "2") (pinfunction "CD/DAT3_2") (pintype "passive"))
    )
    (net (code "250") (name "unconnected-(J1-DAT1-Pad8)") (class "Default")
      (node (ref "J1") (pin "8") (pinfunction "DAT1_8") (pintype "passive"))
    )
    (net (code "251") (name "unconnected-(J1-DAT2-Pad1)") (class "Default")
      (node (ref "J1") (pin "1") (pinfunction "DAT2_1") (pintype "passive"))
    )
    (net (code "252") (name "unconnected-(LCD1-NC1-Pad35)") (class "Default")
      (node (ref "LCD1") (pin "35") (pinfunction "NC1_35") (pintype "no_connect"))
    )
    (net (code "253") (name "~{FAULT}") (class "Default")
      (node (ref "IC3") (pin "1") (pinfunction "~{FAULT}_1") (pintype "output"))
      (node (ref "IC4") (pin "58") (pinfunction "PB2_58") (pintype "bidirectional"))
      (node (ref "R13") (pin "2") (pinfunction "2_2") (pintype "passive"))
      (node (ref "X1") (pin "8") (pinfunction "1_8") (pintype "passive"))
      (node (ref "X2") (pin "15") (pinfunction "1_15") (pintype "passive"))
    )
    (net (code "254") (name "~{RESET}") (class "Default")
      (node (ref "IC16") (pin "29") (pinfunction "RESET_N_29") (pintype "input"))
      (node (ref "IC3") (pin "4") (pinfunction "ENA_4") (pintype "input"))
      (node (ref "IC4") (pin "31") (pinfunction "NRST_31") (pintype "bidirectional"))
      (node (ref "IC6") (pin "4") (pinfunction "IO3_4") (pintype "bidirectional"))
      (node (ref "JP5") (pin "NO") (pinfunction "NO_NO") (pintype "passive"))
      (node (ref "R11") (pin "2") (pinfunction "2_2") (pintype "passive"))
      (node (ref "X1") (pin "6") (pinfunction "1_6") (pintype "passive"))
      (node (ref "X4") (pin "5") (pinfunction "S_5") (pintype "passive"))
    )
    (net (code "255") (name "~{USB_OTG_FS_OC}") (class "Default")
      (node (ref "IC4") (pin "146") (pinfunction "PD4_146") (pintype "bidirectional"))
      (node (ref "IC9") (pin "3") (pinfunction "~{OC}_3") (pintype "passive"))
      (node (ref "R28") (pin "1") (pinfunction "1_1") (pintype "passive"))
    )
  )
)
